# PCB-CMB-5-SHLD.net
KiCad netlist of a schematic drawn in EAGLE
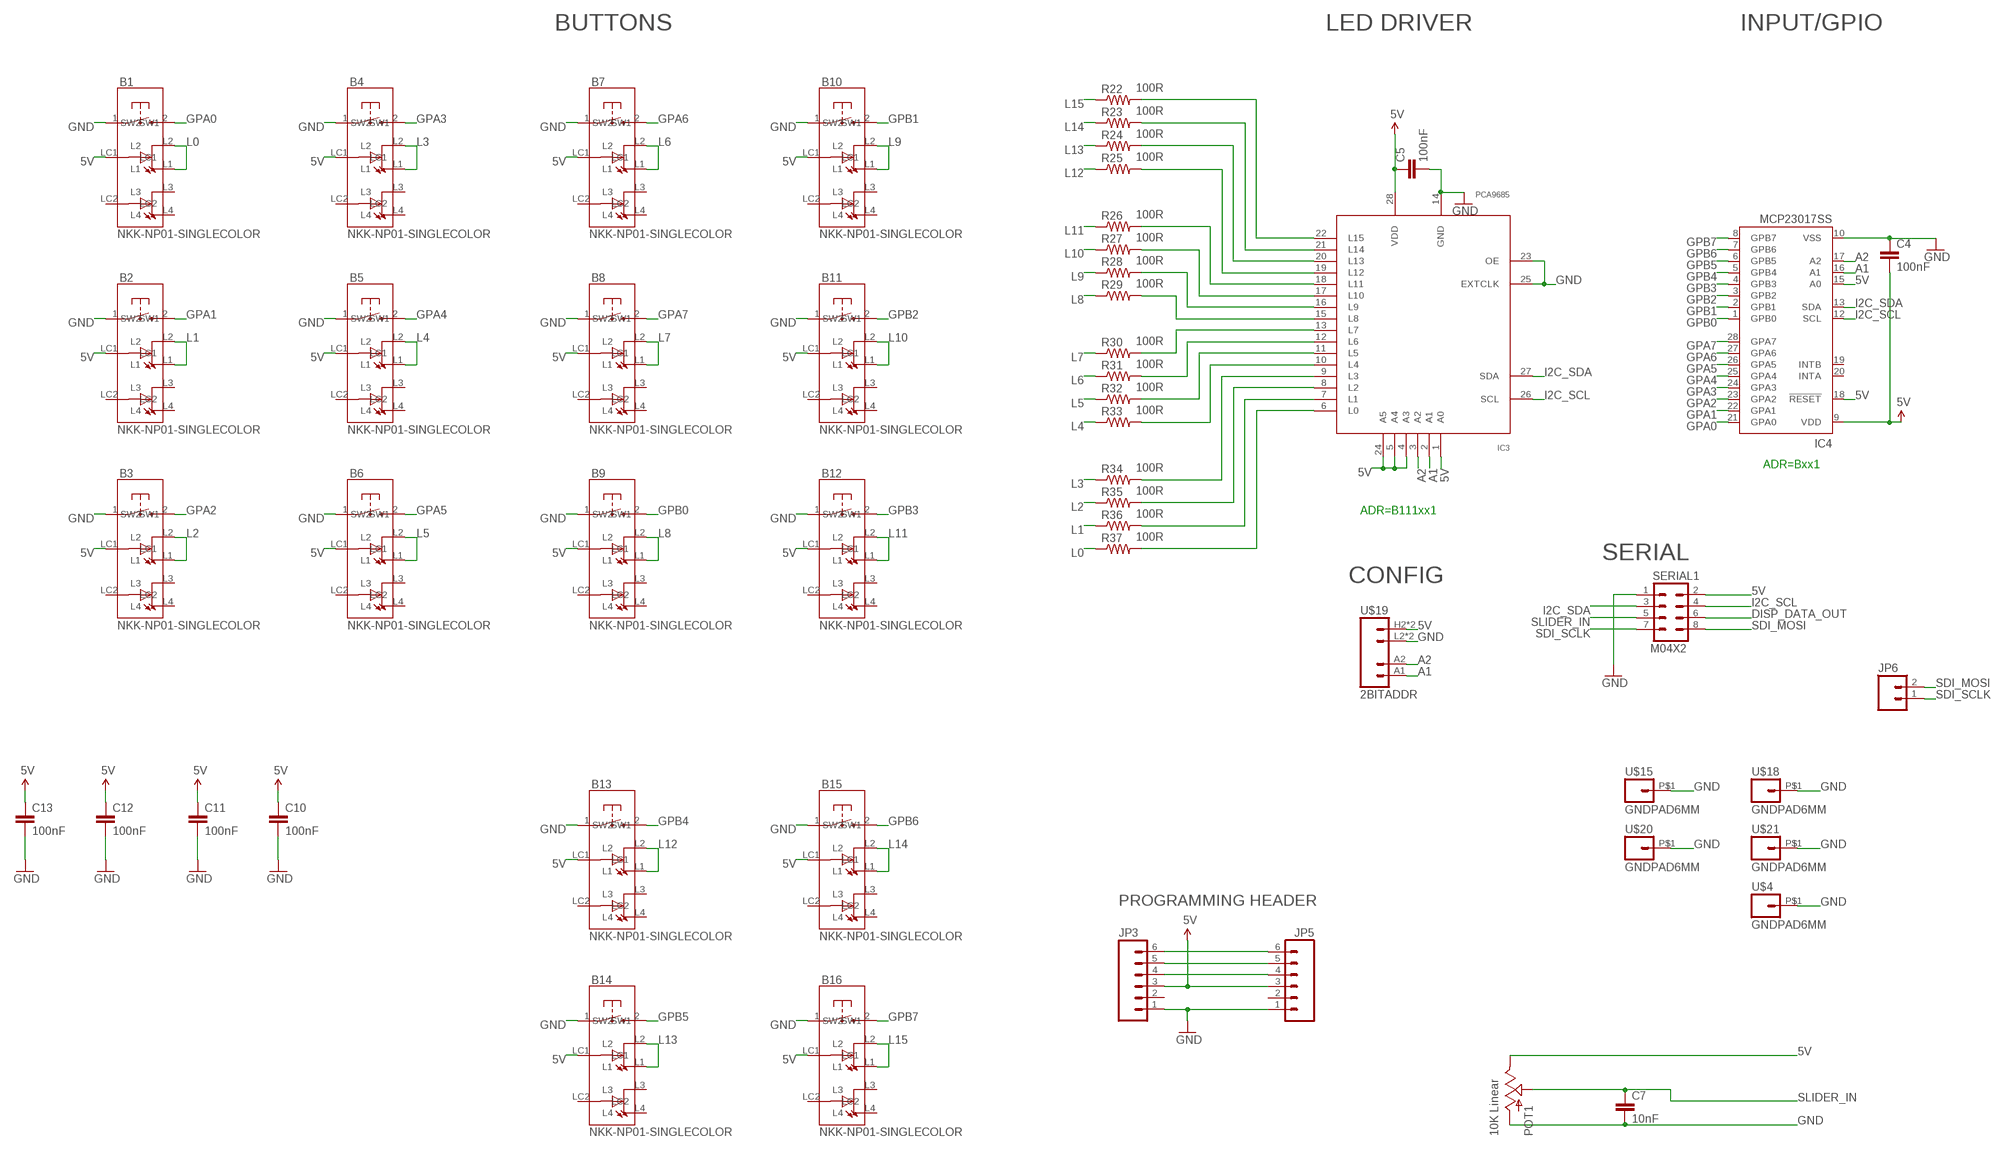
[diagram p0: schematic, sheet 1, part 1 of 3]
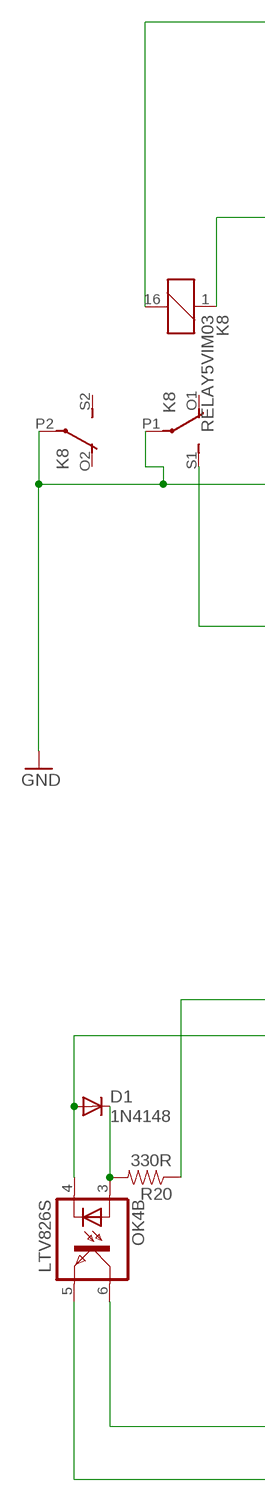
[diagram p1: schematic, sheet 1, part 2 of 3]
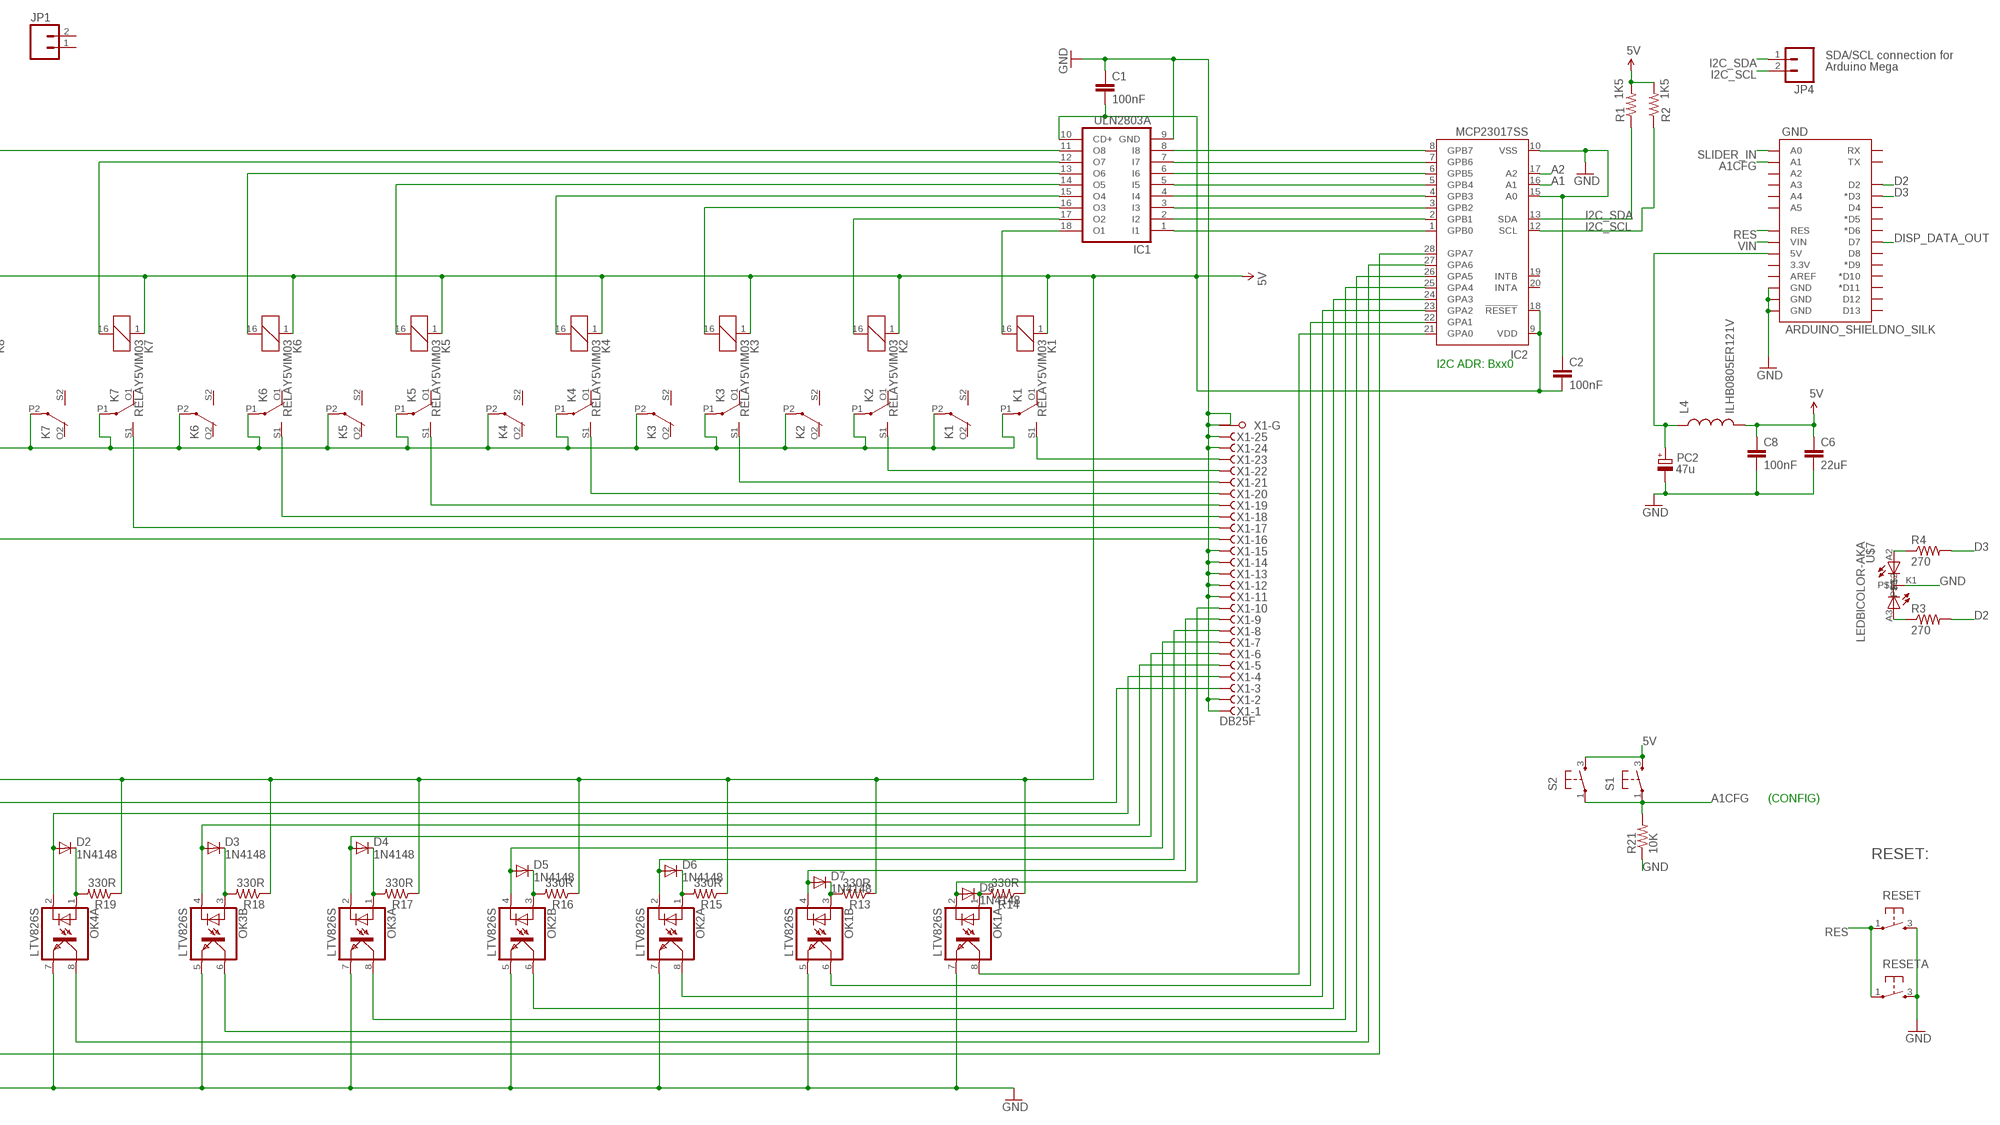
[diagram p2: schematic, sheet 1, part 3 of 3]

(export (version "E")
  (design (tool "Eeschema 10.0.6"))
  (components
    (comp (ref "B1")
      (value "NKK-NP01-SINGLECOLOR")
      (footprint "eagle-import:NKK-NP01")
      (libsource (lib "eagle-import") (part "NKK-NP01-SINGLECOLOR"))
    )
    (comp (ref "B2")
      (value "NKK-NP01-SINGLECOLOR")
      (footprint "eagle-import:NKK-NP01")
      (libsource (lib "eagle-import") (part "NKK-NP01-SINGLECOLOR"))
    )
    (comp (ref "B3")
      (value "NKK-NP01-SINGLECOLOR")
      (footprint "eagle-import:NKK-NP01")
      (libsource (lib "eagle-import") (part "NKK-NP01-SINGLECOLOR"))
    )
    (comp (ref "B4")
      (value "NKK-NP01-SINGLECOLOR")
      (footprint "eagle-import:NKK-NP01")
      (libsource (lib "eagle-import") (part "NKK-NP01-SINGLECOLOR"))
    )
    (comp (ref "B5")
      (value "NKK-NP01-SINGLECOLOR")
      (footprint "eagle-import:NKK-NP01")
      (libsource (lib "eagle-import") (part "NKK-NP01-SINGLECOLOR"))
    )
    (comp (ref "B6")
      (value "NKK-NP01-SINGLECOLOR")
      (footprint "eagle-import:NKK-NP01")
      (libsource (lib "eagle-import") (part "NKK-NP01-SINGLECOLOR"))
    )
    (comp (ref "B7")
      (value "NKK-NP01-SINGLECOLOR")
      (footprint "eagle-import:NKK-NP01")
      (libsource (lib "eagle-import") (part "NKK-NP01-SINGLECOLOR"))
    )
    (comp (ref "B8")
      (value "NKK-NP01-SINGLECOLOR")
      (footprint "eagle-import:NKK-NP01")
      (libsource (lib "eagle-import") (part "NKK-NP01-SINGLECOLOR"))
    )
    (comp (ref "B9")
      (value "NKK-NP01-SINGLECOLOR")
      (footprint "eagle-import:NKK-NP01")
      (libsource (lib "eagle-import") (part "NKK-NP01-SINGLECOLOR"))
    )
    (comp (ref "B10")
      (value "NKK-NP01-SINGLECOLOR")
      (footprint "eagle-import:NKK-NP01")
      (libsource (lib "eagle-import") (part "NKK-NP01-SINGLECOLOR"))
    )
    (comp (ref "B11")
      (value "NKK-NP01-SINGLECOLOR")
      (footprint "eagle-import:NKK-NP01")
      (libsource (lib "eagle-import") (part "NKK-NP01-SINGLECOLOR"))
    )
    (comp (ref "B12")
      (value "NKK-NP01-SINGLECOLOR")
      (footprint "eagle-import:NKK-NP01")
      (libsource (lib "eagle-import") (part "NKK-NP01-SINGLECOLOR"))
    )
    (comp (ref "B13")
      (value "NKK-NP01-SINGLECOLOR")
      (footprint "eagle-import:NKK-NP01")
      (libsource (lib "eagle-import") (part "NKK-NP01-SINGLECOLOR"))
    )
    (comp (ref "B14")
      (value "NKK-NP01-SINGLECOLOR")
      (footprint "eagle-import:NKK-NP01")
      (libsource (lib "eagle-import") (part "NKK-NP01-SINGLECOLOR"))
    )
    (comp (ref "B15")
      (value "NKK-NP01-SINGLECOLOR")
      (footprint "eagle-import:NKK-NP01")
      (libsource (lib "eagle-import") (part "NKK-NP01-SINGLECOLOR"))
    )
    (comp (ref "B16")
      (value "NKK-NP01-SINGLECOLOR")
      (footprint "eagle-import:NKK-NP01")
      (libsource (lib "eagle-import") (part "NKK-NP01-SINGLECOLOR"))
    )
    (comp (ref "C1")
      (value "100nF")
      (footprint "eagle-import:0805")
      (libsource (lib "eagle-import") (part "CAP0805"))
    )
    (comp (ref "C2")
      (value "100nF")
      (footprint "eagle-import:0603-CAP")
      (libsource (lib "eagle-import") (part "CAP0603-CAP"))
    )
    (comp (ref "C4")
      (value "100nF")
      (footprint "eagle-import:0603-CAP")
      (libsource (lib "eagle-import") (part "CAP0603-CAP"))
    )
    (comp (ref "C5")
      (value "100nF")
      (footprint "eagle-import:0603-CAP")
      (libsource (lib "eagle-import") (part "CAP0603-CAP"))
    )
    (comp (ref "C6")
      (value "22uF")
      (footprint "eagle-import:0805")
      (libsource (lib "eagle-import") (part "CAP0805"))
    )
    (comp (ref "C7")
      (value "10nF")
      (footprint "eagle-import:0603-CAP")
      (libsource (lib "eagle-import") (part "CAP0603-CAP"))
    )
    (comp (ref "C8")
      (value "100nF")
      (footprint "eagle-import:0603-CAP")
      (libsource (lib "eagle-import") (part "CAP0603-CAP"))
    )
    (comp (ref "C10")
      (value "100nF")
      (footprint "eagle-import:0603-CAP")
      (libsource (lib "eagle-import") (part "CAP0603-CAP"))
    )
    (comp (ref "C11")
      (value "100nF")
      (footprint "eagle-import:0603-CAP")
      (libsource (lib "eagle-import") (part "CAP0603-CAP"))
    )
    (comp (ref "C12")
      (value "100nF")
      (footprint "eagle-import:0603-CAP")
      (libsource (lib "eagle-import") (part "CAP0603-CAP"))
    )
    (comp (ref "C13")
      (value "100nF")
      (footprint "eagle-import:0603-CAP")
      (libsource (lib "eagle-import") (part "CAP0603-CAP"))
    )
    (comp (ref "D1")
      (value "1N4148")
      (footprint "eagle-import:SOD-323")
      (libsource (lib "eagle-import") (part "DIODESOD"))
    )
    (comp (ref "D2")
      (value "1N4148")
      (footprint "eagle-import:SOD-323")
      (libsource (lib "eagle-import") (part "DIODESOD"))
    )
    (comp (ref "D3")
      (value "1N4148")
      (footprint "eagle-import:SOD-323")
      (libsource (lib "eagle-import") (part "DIODESOD"))
    )
    (comp (ref "D4")
      (value "1N4148")
      (footprint "eagle-import:SOD-323")
      (libsource (lib "eagle-import") (part "DIODESOD"))
    )
    (comp (ref "D5")
      (value "1N4148")
      (footprint "eagle-import:SOD-323")
      (libsource (lib "eagle-import") (part "DIODESOD"))
    )
    (comp (ref "D6")
      (value "1N4148")
      (footprint "eagle-import:SOD-323")
      (libsource (lib "eagle-import") (part "DIODESOD"))
    )
    (comp (ref "D7")
      (value "1N4148")
      (footprint "eagle-import:SOD-323")
      (libsource (lib "eagle-import") (part "DIODESOD"))
    )
    (comp (ref "D8")
      (value "1N4148")
      (footprint "eagle-import:SOD-323")
      (libsource (lib "eagle-import") (part "DIODESOD"))
    )
    (comp (ref "GND")
      (value "ARDUINO_SHIELDNO_SILK")
      (footprint "eagle-import:DUEMILANOVE_VIAS")
      (libsource (lib "eagle-import") (part "ARDUINO_SHIELDNO_SILK"))
    )
    (comp (ref "IC1")
      (value "ULN2803A")
      (footprint "eagle-import:SO18W")
      (libsource (lib "eagle-import") (part "ULN2803ASO18W"))
    )
    (comp (ref "IC2")
      (value "MCP23017SS")
      (footprint "eagle-import:SSOP28")
      (fields (field (name "MF") "MICROCHIP") (field (name "MPN") "MCP23017-E/SS"))
      (libsource (lib "eagle-import") (part "MCP23017SS"))
    )
    (comp (ref "IC3")
      (value "PCA9685")
      (footprint "eagle-import:TSSOP28")
      (libsource (lib "eagle-import") (part "PCA9685"))
    )
    (comp (ref "IC4")
      (value "MCP23017SS")
      (footprint "eagle-import:SSOP28")
      (fields
        (field (name "MF") "MICROCHIP")
        (field (name "MPN") "MCP23017-E/SS")
        (field (name "MPN_1") "MCP23017-E/SS")
        (field (name "OC_FARNELL") "1467674")
        (field (name "OC_NEWARK") "31K2960")
      )
      (libsource (lib "eagle-import") (part "MCP23017SS"))
    )
    (comp (ref "JP1")
      (value "M02PTH")
      (footprint "eagle-import:1X02")
      (libsource (lib "eagle-import") (part "M02PTH"))
    )
    (comp (ref "JP3")
      (value "M06POLAR")
      (footprint "eagle-import:MOLEX-1X6")
      (libsource (lib "eagle-import") (part "M06POLAR"))
    )
    (comp (ref "JP4")
      (value "M02PTH")
      (footprint "eagle-import:1X02")
      (libsource (lib "eagle-import") (part "M02PTH"))
    )
    (comp (ref "JP5")
      (value "M06POLAR")
      (footprint "eagle-import:MOLEX-1X6")
      (libsource (lib "eagle-import") (part "M06POLAR"))
    )
    (comp (ref "JP6")
      (value "M02PTH")
      (footprint "eagle-import:1X02")
      (libsource (lib "eagle-import") (part "M02PTH"))
    )
    (comp (ref "K1")
      (value "RELAY5VIM03")
      (footprint "eagle-import:DS2Y")
      (libsource (lib "eagle-import") (part "RELAY5VIM03"))
    )
    (comp (ref "K2")
      (value "RELAY5VIM03")
      (footprint "eagle-import:DS2Y")
      (libsource (lib "eagle-import") (part "RELAY5VIM03"))
    )
    (comp (ref "K3")
      (value "RELAY5VIM03")
      (footprint "eagle-import:DS2Y")
      (libsource (lib "eagle-import") (part "RELAY5VIM03"))
    )
    (comp (ref "K4")
      (value "RELAY5VIM03")
      (footprint "eagle-import:DS2Y")
      (libsource (lib "eagle-import") (part "RELAY5VIM03"))
    )
    (comp (ref "K5")
      (value "RELAY5VIM03")
      (footprint "eagle-import:DS2Y")
      (libsource (lib "eagle-import") (part "RELAY5VIM03"))
    )
    (comp (ref "K6")
      (value "RELAY5VIM03")
      (footprint "eagle-import:DS2Y")
      (libsource (lib "eagle-import") (part "RELAY5VIM03"))
    )
    (comp (ref "K7")
      (value "RELAY5VIM03")
      (footprint "eagle-import:DS2Y")
      (libsource (lib "eagle-import") (part "RELAY5VIM03"))
    )
    (comp (ref "K8")
      (value "RELAY5VIM03")
      (footprint "eagle-import:DS2Y")
      (libsource (lib "eagle-import") (part "RELAY5VIM03"))
    )
    (comp (ref "L4")
      (value "ILHB0805ER121V")
      (footprint "eagle-import:0805")
      (libsource (lib "eagle-import") (part "INDUCTOR0805"))
    )
    (comp (ref "OK1")
      (value "LTV826S")
      (footprint "eagle-import:DIL8-SMD")
      (libsource (lib "eagle-import") (part "LTV826S"))
    )
    (comp (ref "OK2")
      (value "LTV826S")
      (footprint "eagle-import:DIL8-SMD")
      (libsource (lib "eagle-import") (part "LTV826S"))
    )
    (comp (ref "OK3")
      (value "LTV826S")
      (footprint "eagle-import:DIL8-SMD")
      (libsource (lib "eagle-import") (part "LTV826S"))
    )
    (comp (ref "OK4")
      (value "LTV826S")
      (footprint "eagle-import:DIL8-SMD")
      (libsource (lib "eagle-import") (part "LTV826S"))
    )
    (comp (ref "PC2")
      (value "47u")
      (footprint "eagle-import:PANASONIC_D")
      (libsource (lib "eagle-import") (part "CPOL-EUD"))
    )
    (comp (ref "POT1")
      (value "10K Linear")
      (footprint "eagle-import:SLIDER20")
      (libsource (lib "eagle-import") (part "SLIDER20"))
    )
    (comp (ref "R1")
      (value "1K5")
      (footprint "eagle-import:0603-RES")
      (libsource (lib "eagle-import") (part "RESISTOR0603-RES"))
    )
    (comp (ref "R2")
      (value "1K5")
      (footprint "eagle-import:0603-RES")
      (libsource (lib "eagle-import") (part "RESISTOR0603-RES"))
    )
    (comp (ref "R3")
      (value "270")
      (footprint "eagle-import:0603-RES")
      (libsource (lib "eagle-import") (part "RESISTOR0603-RES"))
    )
    (comp (ref "R4")
      (value "270")
      (footprint "eagle-import:0603-RES")
      (libsource (lib "eagle-import") (part "RESISTOR0603-RES"))
    )
    (comp (ref "R13")
      (value "330R")
      (footprint "eagle-import:0603-RES")
      (libsource (lib "eagle-import") (part "RESISTOR0603-RES"))
    )
    (comp (ref "R14")
      (value "330R")
      (footprint "eagle-import:0603-RES")
      (libsource (lib "eagle-import") (part "RESISTOR0603-RES"))
    )
    (comp (ref "R15")
      (value "330R")
      (footprint "eagle-import:0603-RES")
      (libsource (lib "eagle-import") (part "RESISTOR0603-RES"))
    )
    (comp (ref "R16")
      (value "330R")
      (footprint "eagle-import:0603-RES")
      (libsource (lib "eagle-import") (part "RESISTOR0603-RES"))
    )
    (comp (ref "R17")
      (value "330R")
      (footprint "eagle-import:0603-RES")
      (libsource (lib "eagle-import") (part "RESISTOR0603-RES"))
    )
    (comp (ref "R18")
      (value "330R")
      (footprint "eagle-import:0603-RES")
      (libsource (lib "eagle-import") (part "RESISTOR0603-RES"))
    )
    (comp (ref "R19")
      (value "330R")
      (footprint "eagle-import:0603-RES")
      (libsource (lib "eagle-import") (part "RESISTOR0603-RES"))
    )
    (comp (ref "R20")
      (value "330R")
      (footprint "eagle-import:0603-RES")
      (libsource (lib "eagle-import") (part "RESISTOR0603-RES"))
    )
    (comp (ref "R21")
      (value "10K")
      (footprint "eagle-import:0603-RES")
      (libsource (lib "eagle-import") (part "RESISTOR0603-RES"))
    )
    (comp (ref "R22")
      (value "100R")
      (footprint "eagle-import:0603-RES")
      (libsource (lib "eagle-import") (part "RESISTOR0603-RES"))
    )
    (comp (ref "R23")
      (value "100R")
      (footprint "eagle-import:0603-RES")
      (libsource (lib "eagle-import") (part "RESISTOR0603-RES"))
    )
    (comp (ref "R24")
      (value "100R")
      (footprint "eagle-import:0603-RES")
      (libsource (lib "eagle-import") (part "RESISTOR0603-RES"))
    )
    (comp (ref "R25")
      (value "100R")
      (footprint "eagle-import:0603-RES")
      (libsource (lib "eagle-import") (part "RESISTOR0603-RES"))
    )
    (comp (ref "R26")
      (value "100R")
      (footprint "eagle-import:0603-RES")
      (libsource (lib "eagle-import") (part "RESISTOR0603-RES"))
    )
    (comp (ref "R27")
      (value "100R")
      (footprint "eagle-import:0603-RES")
      (libsource (lib "eagle-import") (part "RESISTOR0603-RES"))
    )
    (comp (ref "R28")
      (value "100R")
      (footprint "eagle-import:0603-RES")
      (libsource (lib "eagle-import") (part "RESISTOR0603-RES"))
    )
    (comp (ref "R29")
      (value "100R")
      (footprint "eagle-import:0603-RES")
      (libsource (lib "eagle-import") (part "RESISTOR0603-RES"))
    )
    (comp (ref "R30")
      (value "100R")
      (footprint "eagle-import:0603-RES")
      (libsource (lib "eagle-import") (part "RESISTOR0603-RES"))
    )
    (comp (ref "R31")
      (value "100R")
      (footprint "eagle-import:0603-RES")
      (libsource (lib "eagle-import") (part "RESISTOR0603-RES"))
    )
    (comp (ref "R32")
      (value "100R")
      (footprint "eagle-import:0603-RES")
      (libsource (lib "eagle-import") (part "RESISTOR0603-RES"))
    )
    (comp (ref "R33")
      (value "100R")
      (footprint "eagle-import:0603-RES")
      (libsource (lib "eagle-import") (part "RESISTOR0603-RES"))
    )
    (comp (ref "R34")
      (value "100R")
      (footprint "eagle-import:0603-RES")
      (libsource (lib "eagle-import") (part "RESISTOR0603-RES"))
    )
    (comp (ref "R35")
      (value "100R")
      (footprint "eagle-import:0603-RES")
      (libsource (lib "eagle-import") (part "RESISTOR0603-RES"))
    )
    (comp (ref "R36")
      (value "100R")
      (footprint "eagle-import:0603-RES")
      (libsource (lib "eagle-import") (part "RESISTOR0603-RES"))
    )
    (comp (ref "R37")
      (value "100R")
      (footprint "eagle-import:0603-RES")
      (libsource (lib "eagle-import") (part "RESISTOR0603-RES"))
    )
    (comp (ref "RESET")
      (value "TAC_SWITCH")
      (footprint "eagle-import:PUSHBUTTON")
      (libsource (lib "eagle-import") (part "TAC_SWITCH"))
    )
    (comp (ref "RESETA")
      (value "TAC_SWITCH")
      (footprint "eagle-import:PUSHBUTTON")
      (libsource (lib "eagle-import") (part "TAC_SWITCH"))
    )
    (comp (ref "S1")
      (value "TAC_SWITCH")
      (footprint "eagle-import:PUSHBUTTON")
      (libsource (lib "eagle-import") (part "TAC_SWITCH"))
    )
    (comp (ref "S2")
      (value "TAC_SWITCH")
      (footprint "eagle-import:PUSHBUTTON")
      (libsource (lib "eagle-import") (part "TAC_SWITCH"))
    )
    (comp (ref "SERIAL1")
      (value "M04X2")
      (footprint "eagle-import:2X4")
      (libsource (lib "eagle-import") (part "M04X2"))
    )
    (comp (ref "U$4")
      (value "GNDPAD6MM")
      (footprint "eagle-import:3.2MMPAD6MM")
      (libsource (lib "eagle-import") (part "GNDPAD6MM"))
    )
    (comp (ref "U$7")
      (value "LEDBICOLOR-AKA")
      (footprint "eagle-import:LED5MM-BICOLOR")
      (libsource (lib "eagle-import") (part "LEDBICOLOR-AKA"))
    )
    (comp (ref "U$15")
      (value "GNDPAD6MM")
      (footprint "eagle-import:3.2MMPAD6MM")
      (libsource (lib "eagle-import") (part "GNDPAD6MM"))
    )
    (comp (ref "U$18")
      (value "GNDPAD6MM")
      (footprint "eagle-import:3.2MMPAD6MM")
      (libsource (lib "eagle-import") (part "GNDPAD6MM"))
    )
    (comp (ref "U$19")
      (value "2BITADDR")
      (footprint "eagle-import:2BITADDR")
      (libsource (lib "eagle-import") (part "2BITADDR"))
    )
    (comp (ref "U$20")
      (value "GNDPAD6MM")
      (footprint "eagle-import:3.2MMPAD6MM")
      (libsource (lib "eagle-import") (part "GNDPAD6MM"))
    )
    (comp (ref "U$21")
      (value "GNDPAD6MM")
      (footprint "eagle-import:3.2MMPAD6MM")
      (libsource (lib "eagle-import") (part "GNDPAD6MM"))
    )
    (comp (ref "X1")
      (value "DB25F")
      (footprint "eagle-import:F25HP")
      (libsource (lib "eagle-import") (part "F25HPS"))
    )
  )
  (nets
    (net (code "1") (name "5V") (class "Default")
      (node (ref "B1") (pin "LC1") (pinfunction "LC1_LC1") (pintype "bidirectional"))
      (node (ref "B10") (pin "LC1") (pinfunction "LC1_LC1") (pintype "bidirectional"))
      (node (ref "B11") (pin "LC1") (pinfunction "LC1_LC1") (pintype "bidirectional"))
      (node (ref "B12") (pin "LC1") (pinfunction "LC1_LC1") (pintype "bidirectional"))
      (node (ref "B13") (pin "LC1") (pinfunction "LC1_LC1") (pintype "bidirectional"))
      (node (ref "B14") (pin "LC1") (pinfunction "LC1_LC1") (pintype "bidirectional"))
      (node (ref "B15") (pin "LC1") (pinfunction "LC1_LC1") (pintype "bidirectional"))
      (node (ref "B16") (pin "LC1") (pinfunction "LC1_LC1") (pintype "bidirectional"))
      (node (ref "B2") (pin "LC1") (pinfunction "LC1_LC1") (pintype "bidirectional"))
      (node (ref "B3") (pin "LC1") (pinfunction "LC1_LC1") (pintype "bidirectional"))
      (node (ref "B4") (pin "LC1") (pinfunction "LC1_LC1") (pintype "bidirectional"))
      (node (ref "B5") (pin "LC1") (pinfunction "LC1_LC1") (pintype "bidirectional"))
      (node (ref "B6") (pin "LC1") (pinfunction "LC1_LC1") (pintype "bidirectional"))
      (node (ref "B7") (pin "LC1") (pinfunction "LC1_LC1") (pintype "bidirectional"))
      (node (ref "B8") (pin "LC1") (pinfunction "LC1_LC1") (pintype "bidirectional"))
      (node (ref "B9") (pin "LC1") (pinfunction "LC1_LC1") (pintype "bidirectional"))
      (node (ref "C1") (pin "2") (pinfunction "2_2") (pintype "passive"))
      (node (ref "C10") (pin "1") (pinfunction "1_1") (pintype "passive"))
      (node (ref "C11") (pin "1") (pinfunction "1_1") (pintype "passive"))
      (node (ref "C12") (pin "1") (pinfunction "1_1") (pintype "passive"))
      (node (ref "C13") (pin "1") (pinfunction "1_1") (pintype "passive"))
      (node (ref "C2") (pin "2") (pinfunction "2_2") (pintype "passive"))
      (node (ref "C4") (pin "2") (pinfunction "2_2") (pintype "passive"))
      (node (ref "C5") (pin "1") (pinfunction "1_1") (pintype "passive"))
      (node (ref "C6") (pin "1") (pinfunction "1_1") (pintype "passive"))
      (node (ref "C8") (pin "1") (pinfunction "1_1") (pintype "passive"))
      (node (ref "IC1") (pin "10") (pinfunction "CD+_10") (pintype "passive"))
      (node (ref "IC2") (pin "18") (pinfunction "~{RESET}_18") (pintype "input"))
      (node (ref "IC2") (pin "9") (pinfunction "VDD_9") (pintype "power_in"))
      (node (ref "IC3") (pin "1") (pinfunction "A0_1") (pintype "input"))
      (node (ref "IC3") (pin "24") (pinfunction "A5_24") (pintype "input"))
      (node (ref "IC3") (pin "28") (pinfunction "VDD_28") (pintype "power_in"))
      (node (ref "IC3") (pin "4") (pinfunction "A3_4") (pintype "input"))
      (node (ref "IC3") (pin "5") (pinfunction "A4_5") (pintype "input"))
      (node (ref "IC4") (pin "15") (pinfunction "A0_15") (pintype "input"))
      (node (ref "IC4") (pin "18") (pinfunction "~{RESET}_18") (pintype "input"))
      (node (ref "IC4") (pin "9") (pinfunction "VDD_9") (pintype "power_in"))
      (node (ref "JP3") (pin "3") (pinfunction "3_3") (pintype "passive"))
      (node (ref "JP5") (pin "3") (pinfunction "3_3") (pintype "passive"))
      (node (ref "K1") (pin "1") (pinfunction "1_1") (pintype "passive"))
      (node (ref "K2") (pin "1") (pinfunction "1_1") (pintype "passive"))
      (node (ref "K3") (pin "1") (pinfunction "1_1") (pintype "passive"))
      (node (ref "K4") (pin "1") (pinfunction "1_1") (pintype "passive"))
      (node (ref "K5") (pin "1") (pinfunction "1_1") (pintype "passive"))
      (node (ref "K6") (pin "1") (pinfunction "1_1") (pintype "passive"))
      (node (ref "K7") (pin "1") (pinfunction "1_1") (pintype "passive"))
      (node (ref "K8") (pin "1") (pinfunction "1_1") (pintype "passive"))
      (node (ref "L4") (pin "2") (pinfunction "2_2") (pintype "passive"))
      (node (ref "POT1") (pin "1") (pinfunction "E_1") (pintype "passive"))
      (node (ref "R1") (pin "2") (pinfunction "2_2") (pintype "passive"))
      (node (ref "R13") (pin "1") (pinfunction "1_1") (pintype "passive"))
      (node (ref "R14") (pin "1") (pinfunction "1_1") (pintype "passive"))
      (node (ref "R15") (pin "1") (pinfunction "1_1") (pintype "passive"))
      (node (ref "R16") (pin "1") (pinfunction "1_1") (pintype "passive"))
      (node (ref "R17") (pin "1") (pinfunction "1_1") (pintype "passive"))
      (node (ref "R18") (pin "1") (pinfunction "1_1") (pintype "passive"))
      (node (ref "R19") (pin "1") (pinfunction "1_1") (pintype "passive"))
      (node (ref "R2") (pin "2") (pinfunction "2_2") (pintype "passive"))
      (node (ref "R20") (pin "1") (pinfunction "1_1") (pintype "passive"))
      (node (ref "S1") (pin "3") (pinfunction "3_3") (pintype "passive"))
      (node (ref "S2") (pin "3") (pinfunction "3_3") (pintype "passive"))
      (node (ref "SERIAL1") (pin "2") (pinfunction "2_2") (pintype "passive"))
      (node (ref "U$19") (pin "H2") (pinfunction "VCC_H2") (pintype "passive"))
      (node (ref "U$19") (pin "H3") (pinfunction "VCC_H3") (pintype "passive"))
    )
    (net (code "2") (name "A1") (class "Default")
      (node (ref "IC2") (pin "16") (pinfunction "A1_16") (pintype "input"))
      (node (ref "IC3") (pin "2") (pinfunction "A1_2") (pintype "input"))
      (node (ref "IC4") (pin "16") (pinfunction "A1_16") (pintype "input"))
      (node (ref "U$19") (pin "A1") (pinfunction "A1_A1") (pintype "passive"))
    )
    (net (code "3") (name "A1CFG") (class "Default")
      (node (ref "GND") (pin "A1") (pinfunction "A1_A1") (pintype "bidirectional"))
      (node (ref "R21") (pin "2") (pinfunction "2_2") (pintype "passive"))
      (node (ref "S1") (pin "1") (pinfunction "1_1") (pintype "passive"))
      (node (ref "S2") (pin "1") (pinfunction "1_1") (pintype "passive"))
    )
    (net (code "4") (name "A2") (class "Default")
      (node (ref "IC2") (pin "17") (pinfunction "A2_17") (pintype "input"))
      (node (ref "IC3") (pin "3") (pinfunction "A2_3") (pintype "input"))
      (node (ref "IC4") (pin "17") (pinfunction "A2_17") (pintype "input"))
      (node (ref "U$19") (pin "A2") (pinfunction "A2_A2") (pintype "passive"))
    )
    (net (code "5") (name "D2") (class "Default")
      (node (ref "GND") (pin "D2") (pinfunction "D2_D2") (pintype "bidirectional"))
      (node (ref "R3") (pin "2") (pinfunction "2_2") (pintype "passive"))
    )
    (net (code "6") (name "D3") (class "Default")
      (node (ref "GND") (pin "D3") (pinfunction "*D3_D3") (pintype "bidirectional"))
      (node (ref "R4") (pin "2") (pinfunction "2_2") (pintype "passive"))
    )
    (net (code "7") (name "DISP_DATA_OUT") (class "Default")
      (node (ref "GND") (pin "D7") (pinfunction "D7_D7") (pintype "bidirectional"))
      (node (ref "SERIAL1") (pin "6") (pinfunction "6_6") (pintype "passive"))
    )
    (net (code "8") (name "GND") (class "Default")
      (node (ref "B1") (pin "1") (pinfunction "SW1_1") (pintype "bidirectional"))
      (node (ref "B10") (pin "1") (pinfunction "SW1_1") (pintype "bidirectional"))
      (node (ref "B11") (pin "1") (pinfunction "SW1_1") (pintype "bidirectional"))
      (node (ref "B12") (pin "1") (pinfunction "SW1_1") (pintype "bidirectional"))
      (node (ref "B13") (pin "1") (pinfunction "SW1_1") (pintype "bidirectional"))
      (node (ref "B14") (pin "1") (pinfunction "SW1_1") (pintype "bidirectional"))
      (node (ref "B15") (pin "1") (pinfunction "SW1_1") (pintype "bidirectional"))
      (node (ref "B16") (pin "1") (pinfunction "SW1_1") (pintype "bidirectional"))
      (node (ref "B2") (pin "1") (pinfunction "SW1_1") (pintype "bidirectional"))
      (node (ref "B3") (pin "1") (pinfunction "SW1_1") (pintype "bidirectional"))
      (node (ref "B4") (pin "1") (pinfunction "SW1_1") (pintype "bidirectional"))
      (node (ref "B5") (pin "1") (pinfunction "SW1_1") (pintype "bidirectional"))
      (node (ref "B6") (pin "1") (pinfunction "SW1_1") (pintype "bidirectional"))
      (node (ref "B7") (pin "1") (pinfunction "SW1_1") (pintype "bidirectional"))
      (node (ref "B8") (pin "1") (pinfunction "SW1_1") (pintype "bidirectional"))
      (node (ref "B9") (pin "1") (pinfunction "SW1_1") (pintype "bidirectional"))
      (node (ref "C1") (pin "1") (pinfunction "1_1") (pintype "passive"))
      (node (ref "C10") (pin "2") (pinfunction "2_2") (pintype "passive"))
      (node (ref "C11") (pin "2") (pinfunction "2_2") (pintype "passive"))
      (node (ref "C12") (pin "2") (pinfunction "2_2") (pintype "passive"))
      (node (ref "C13") (pin "2") (pinfunction "2_2") (pintype "passive"))
      (node (ref "C2") (pin "1") (pinfunction "1_1") (pintype "passive"))
      (node (ref "C4") (pin "1") (pinfunction "1_1") (pintype "passive"))
      (node (ref "C5") (pin "2") (pinfunction "2_2") (pintype "passive"))
      (node (ref "C6") (pin "2") (pinfunction "2_2") (pintype "passive"))
      (node (ref "C7") (pin "2") (pinfunction "2_2") (pintype "passive"))
      (node (ref "C8") (pin "2") (pinfunction "2_2") (pintype "passive"))
      (node (ref "GND") (pin "GND@0") (pinfunction "GND_GND@0") (pintype "bidirectional"))
      (node (ref "GND") (pin "GND@1") (pinfunction "GND_GND@1") (pintype "bidirectional"))
      (node (ref "GND") (pin "GND@2") (pinfunction "GND_GND@2") (pintype "bidirectional"))
      (node (ref "IC1") (pin "9") (pinfunction "GND_9") (pintype "power_in"))
      (node (ref "IC2") (pin "10") (pinfunction "VSS_10") (pintype "power_in"))
      (node (ref "IC2") (pin "15") (pinfunction "A0_15") (pintype "input"))
      (node (ref "IC3") (pin "14") (pinfunction "GND_14") (pintype "power_in"))
      (node (ref "IC3") (pin "23") (pinfunction "OE_23") (pintype "input"))
      (node (ref "IC3") (pin "25") (pinfunction "EXTCLK_25") (pintype "input"))
      (node (ref "IC4") (pin "10") (pinfunction "VSS_10") (pintype "power_in"))
      (node (ref "JP3") (pin "1") (pinfunction "1_1") (pintype "passive"))
      (node (ref "JP5") (pin "1") (pinfunction "1_1") (pintype "passive"))
      (node (ref "K1") (pin "P1") (pinfunction "P_P1") (pintype "passive"))
      (node (ref "K1") (pin "P2") (pinfunction "P_P2") (pintype "passive"))
      (node (ref "K2") (pin "P1") (pinfunction "P_P1") (pintype "passive"))
      (node (ref "K2") (pin "P2") (pinfunction "P_P2") (pintype "passive"))
      (node (ref "K3") (pin "P1") (pinfunction "P_P1") (pintype "passive"))
      (node (ref "K3") (pin "P2") (pinfunction "P_P2") (pintype "passive"))
      (node (ref "K4") (pin "P1") (pinfunction "P_P1") (pintype "passive"))
      (node (ref "K4") (pin "P2") (pinfunction "P_P2") (pintype "passive"))
      (node (ref "K5") (pin "P1") (pinfunction "P_P1") (pintype "passive"))
      (node (ref "K5") (pin "P2") (pinfunction "P_P2") (pintype "passive"))
      (node (ref "K6") (pin "P1") (pinfunction "P_P1") (pintype "passive"))
      (node (ref "K6") (pin "P2") (pinfunction "P_P2") (pintype "passive"))
      (node (ref "K7") (pin "P1") (pinfunction "P_P1") (pintype "passive"))
      (node (ref "K7") (pin "P2") (pinfunction "P_P2") (pintype "passive"))
      (node (ref "K8") (pin "P1") (pinfunction "P_P1") (pintype "passive"))
      (node (ref "K8") (pin "P2") (pinfunction "P_P2") (pintype "passive"))
      (node (ref "OK1") (pin "5") (pinfunction "EMIT_5") (pintype "passive"))
      (node (ref "OK1") (pin "7") (pinfunction "EMIT_7") (pintype "passive"))
      (node (ref "OK2") (pin "5") (pinfunction "EMIT_5") (pintype "passive"))
      (node (ref "OK2") (pin "7") (pinfunction "EMIT_7") (pintype "passive"))
      (node (ref "OK3") (pin "5") (pinfunction "EMIT_5") (pintype "passive"))
      (node (ref "OK3") (pin "7") (pinfunction "EMIT_7") (pintype "passive"))
      (node (ref "OK4") (pin "5") (pinfunction "EMIT_5") (pintype "passive"))
      (node (ref "OK4") (pin "7") (pinfunction "EMIT_7") (pintype "passive"))
      (node (ref "PC2") (pin "-") (pinfunction "-_-") (pintype "passive"))
      (node (ref "POT1") (pin "3") (pinfunction "A_3") (pintype "passive"))
      (node (ref "R21") (pin "1") (pinfunction "1_1") (pintype "passive"))
      (node (ref "RESET") (pin "3") (pinfunction "3_3") (pintype "passive"))
      (node (ref "RESETA") (pin "3") (pinfunction "3_3") (pintype "passive"))
      (node (ref "SERIAL1") (pin "1") (pinfunction "1_1") (pintype "passive"))
      (node (ref "U$15") (pin "P$1") (pinfunction "1_P$1") (pintype "passive"))
      (node (ref "U$18") (pin "P$1") (pinfunction "1_P$1") (pintype "passive"))
      (node (ref "U$19") (pin "L2") (pinfunction "GND_L2") (pintype "passive"))
      (node (ref "U$19") (pin "L3") (pinfunction "GND_L3") (pintype "passive"))
      (node (ref "U$20") (pin "P$1") (pinfunction "1_P$1") (pintype "passive"))
      (node (ref "U$21") (pin "P$1") (pinfunction "1_P$1") (pintype "passive"))
      (node (ref "U$4") (pin "P$1") (pinfunction "1_P$1") (pintype "passive"))
      (node (ref "U$7") (pin "K1") (pinfunction "P$1_K1") (pintype "bidirectional"))
      (node (ref "X1") (pin "1") (pinfunction "F_1") (pintype "passive"))
      (node (ref "X1") (pin "11") (pinfunction "F_11") (pintype "passive"))
      (node (ref "X1") (pin "12") (pinfunction "F_12") (pintype "passive"))
      (node (ref "X1") (pin "13") (pinfunction "F_13") (pintype "passive"))
      (node (ref "X1") (pin "14") (pinfunction "F_14") (pintype "passive"))
      (node (ref "X1") (pin "15") (pinfunction "F_15") (pintype "passive"))
      (node (ref "X1") (pin "2") (pinfunction "F_2") (pintype "passive"))
      (node (ref "X1") (pin "24") (pinfunction "F_24") (pintype "passive"))
      (node (ref "X1") (pin "25") (pinfunction "F_25") (pintype "passive"))
      (node (ref "X1") (pin "G1") (pinfunction "G1_G1") (pintype "passive"))
      (node (ref "X1") (pin "G2") (pinfunction "G2_G2") (pintype "passive"))
    )
    (net (code "9") (name "GPA0") (class "Default")
      (node (ref "B1") (pin "2") (pinfunction "SW2_2") (pintype "bidirectional"))
      (node (ref "IC4") (pin "21") (pinfunction "GPA0_21") (pintype "bidirectional"))
    )
    (net (code "10") (name "GPA1") (class "Default")
      (node (ref "B2") (pin "2") (pinfunction "SW2_2") (pintype "bidirectional"))
      (node (ref "IC4") (pin "22") (pinfunction "GPA1_22") (pintype "bidirectional"))
    )
    (net (code "11") (name "GPA2") (class "Default")
      (node (ref "B3") (pin "2") (pinfunction "SW2_2") (pintype "bidirectional"))
      (node (ref "IC4") (pin "23") (pinfunction "GPA2_23") (pintype "bidirectional"))
    )
    (net (code "12") (name "GPA3") (class "Default")
      (node (ref "B4") (pin "2") (pinfunction "SW2_2") (pintype "bidirectional"))
      (node (ref "IC4") (pin "24") (pinfunction "GPA3_24") (pintype "bidirectional"))
    )
    (net (code "13") (name "GPA4") (class "Default")
      (node (ref "B5") (pin "2") (pinfunction "SW2_2") (pintype "bidirectional"))
      (node (ref "IC4") (pin "25") (pinfunction "GPA4_25") (pintype "bidirectional"))
    )
    (net (code "14") (name "GPA5") (class "Default")
      (node (ref "B6") (pin "2") (pinfunction "SW2_2") (pintype "bidirectional"))
      (node (ref "IC4") (pin "26") (pinfunction "GPA5_26") (pintype "bidirectional"))
    )
    (net (code "15") (name "GPA6") (class "Default")
      (node (ref "B7") (pin "2") (pinfunction "SW2_2") (pintype "bidirectional"))
      (node (ref "IC4") (pin "27") (pinfunction "GPA6_27") (pintype "bidirectional"))
    )
    (net (code "16") (name "GPA7") (class "Default")
      (node (ref "B8") (pin "2") (pinfunction "SW2_2") (pintype "bidirectional"))
      (node (ref "IC4") (pin "28") (pinfunction "GPA7_28") (pintype "bidirectional"))
    )
    (net (code "17") (name "GPB0") (class "Default")
      (node (ref "B9") (pin "2") (pinfunction "SW2_2") (pintype "bidirectional"))
      (node (ref "IC4") (pin "1") (pinfunction "GPB0_1") (pintype "bidirectional"))
    )
    (net (code "18") (name "GPB1") (class "Default")
      (node (ref "B10") (pin "2") (pinfunction "SW2_2") (pintype "bidirectional"))
      (node (ref "IC4") (pin "2") (pinfunction "GPB1_2") (pintype "bidirectional"))
    )
    (net (code "19") (name "GPB2") (class "Default")
      (node (ref "B11") (pin "2") (pinfunction "SW2_2") (pintype "bidirectional"))
      (node (ref "IC4") (pin "3") (pinfunction "GPB2_3") (pintype "bidirectional"))
    )
    (net (code "20") (name "GPB3") (class "Default")
      (node (ref "B12") (pin "2") (pinfunction "SW2_2") (pintype "bidirectional"))
      (node (ref "IC4") (pin "4") (pinfunction "GPB3_4") (pintype "bidirectional"))
    )
    (net (code "21") (name "GPB4") (class "Default")
      (node (ref "B13") (pin "2") (pinfunction "SW2_2") (pintype "bidirectional"))
      (node (ref "IC4") (pin "5") (pinfunction "GPB4_5") (pintype "bidirectional"))
    )
    (net (code "22") (name "GPB5") (class "Default")
      (node (ref "B14") (pin "2") (pinfunction "SW2_2") (pintype "bidirectional"))
      (node (ref "IC4") (pin "6") (pinfunction "GPB5_6") (pintype "bidirectional"))
    )
    (net (code "23") (name "GPB6") (class "Default")
      (node (ref "B15") (pin "2") (pinfunction "SW2_2") (pintype "bidirectional"))
      (node (ref "IC4") (pin "7") (pinfunction "GPB6_7") (pintype "bidirectional"))
    )
    (net (code "24") (name "GPB7") (class "Default")
      (node (ref "B16") (pin "2") (pinfunction "SW2_2") (pintype "bidirectional"))
      (node (ref "IC4") (pin "8") (pinfunction "GPB7_8") (pintype "bidirectional"))
    )
    (net (code "25") (name "I2C_SCL") (class "Default")
      (node (ref "IC2") (pin "12") (pinfunction "SCL_12") (pintype "input"))
      (node (ref "IC3") (pin "26") (pinfunction "SCL_26") (pintype "input"))
      (node (ref "IC4") (pin "12") (pinfunction "SCL_12") (pintype "input"))
      (node (ref "JP4") (pin "2") (pinfunction "2_2") (pintype "passive"))
      (node (ref "R2") (pin "1") (pinfunction "1_1") (pintype "passive"))
      (node (ref "SERIAL1") (pin "4") (pinfunction "4_4") (pintype "passive"))
    )
    (net (code "26") (name "I2C_SDA") (class "Default")
      (node (ref "IC2") (pin "13") (pinfunction "SDA_13") (pintype "bidirectional"))
      (node (ref "IC3") (pin "27") (pinfunction "SDA_27") (pintype "input"))
      (node (ref "IC4") (pin "13") (pinfunction "SDA_13") (pintype "bidirectional"))
      (node (ref "JP4") (pin "1") (pinfunction "1_1") (pintype "passive"))
      (node (ref "R1") (pin "1") (pinfunction "1_1") (pintype "passive"))
      (node (ref "SERIAL1") (pin "3") (pinfunction "3_3") (pintype "passive"))
    )
    (net (code "27") (name "L0") (class "Default")
      (node (ref "B1") (pin "L1") (pinfunction "L1_L1") (pintype "bidirectional"))
      (node (ref "B1") (pin "L2") (pinfunction "L2_L2") (pintype "bidirectional"))
      (node (ref "R37") (pin "1") (pinfunction "1_1") (pintype "passive"))
    )
    (net (code "28") (name "L1") (class "Default")
      (node (ref "B2") (pin "L1") (pinfunction "L1_L1") (pintype "bidirectional"))
      (node (ref "B2") (pin "L2") (pinfunction "L2_L2") (pintype "bidirectional"))
      (node (ref "R36") (pin "1") (pinfunction "1_1") (pintype "passive"))
    )
    (net (code "29") (name "L2") (class "Default")
      (node (ref "B3") (pin "L1") (pinfunction "L1_L1") (pintype "bidirectional"))
      (node (ref "B3") (pin "L2") (pinfunction "L2_L2") (pintype "bidirectional"))
      (node (ref "R35") (pin "1") (pinfunction "1_1") (pintype "passive"))
    )
    (net (code "30") (name "L3") (class "Default")
      (node (ref "B4") (pin "L1") (pinfunction "L1_L1") (pintype "bidirectional"))
      (node (ref "B4") (pin "L2") (pinfunction "L2_L2") (pintype "bidirectional"))
      (node (ref "R34") (pin "1") (pinfunction "1_1") (pintype "passive"))
    )
    (net (code "31") (name "L4") (class "Default")
      (node (ref "B5") (pin "L1") (pinfunction "L1_L1") (pintype "bidirectional"))
      (node (ref "B5") (pin "L2") (pinfunction "L2_L2") (pintype "bidirectional"))
      (node (ref "R33") (pin "1") (pinfunction "1_1") (pintype "passive"))
    )
    (net (code "32") (name "L5") (class "Default")
      (node (ref "B6") (pin "L1") (pinfunction "L1_L1") (pintype "bidirectional"))
      (node (ref "B6") (pin "L2") (pinfunction "L2_L2") (pintype "bidirectional"))
      (node (ref "R32") (pin "1") (pinfunction "1_1") (pintype "passive"))
    )
    (net (code "33") (name "L6") (class "Default")
      (node (ref "B7") (pin "L1") (pinfunction "L1_L1") (pintype "bidirectional"))
      (node (ref "B7") (pin "L2") (pinfunction "L2_L2") (pintype "bidirectional"))
      (node (ref "R31") (pin "1") (pinfunction "1_1") (pintype "passive"))
    )
    (net (code "34") (name "L7") (class "Default")
      (node (ref "B8") (pin "L1") (pinfunction "L1_L1") (pintype "bidirectional"))
      (node (ref "B8") (pin "L2") (pinfunction "L2_L2") (pintype "bidirectional"))
      (node (ref "R30") (pin "1") (pinfunction "1_1") (pintype "passive"))
    )
    (net (code "35") (name "L8") (class "Default")
      (node (ref "B9") (pin "L1") (pinfunction "L1_L1") (pintype "bidirectional"))
      (node (ref "B9") (pin "L2") (pinfunction "L2_L2") (pintype "bidirectional"))
      (node (ref "R29") (pin "1") (pinfunction "1_1") (pintype "passive"))
    )
    (net (code "36") (name "L9") (class "Default")
      (node (ref "B10") (pin "L1") (pinfunction "L1_L1") (pintype "bidirectional"))
      (node (ref "B10") (pin "L2") (pinfunction "L2_L2") (pintype "bidirectional"))
      (node (ref "R28") (pin "1") (pinfunction "1_1") (pintype "passive"))
    )
    (net (code "37") (name "L10") (class "Default")
      (node (ref "B11") (pin "L1") (pinfunction "L1_L1") (pintype "bidirectional"))
      (node (ref "B11") (pin "L2") (pinfunction "L2_L2") (pintype "bidirectional"))
      (node (ref "R27") (pin "1") (pinfunction "1_1") (pintype "passive"))
    )
    (net (code "38") (name "L11") (class "Default")
      (node (ref "B12") (pin "L1") (pinfunction "L1_L1") (pintype "bidirectional"))
      (node (ref "B12") (pin "L2") (pinfunction "L2_L2") (pintype "bidirectional"))
      (node (ref "R26") (pin "1") (pinfunction "1_1") (pintype "passive"))
    )
    (net (code "39") (name "L12") (class "Default")
      (node (ref "B13") (pin "L1") (pinfunction "L1_L1") (pintype "bidirectional"))
      (node (ref "B13") (pin "L2") (pinfunction "L2_L2") (pintype "bidirectional"))
      (node (ref "R25") (pin "1") (pinfunction "1_1") (pintype "passive"))
    )
    (net (code "40") (name "L13") (class "Default")
      (node (ref "B14") (pin "L1") (pinfunction "L1_L1") (pintype "bidirectional"))
      (node (ref "B14") (pin "L2") (pinfunction "L2_L2") (pintype "bidirectional"))
      (node (ref "R24") (pin "1") (pinfunction "1_1") (pintype "passive"))
    )
    (net (code "41") (name "L14") (class "Default")
      (node (ref "B15") (pin "L1") (pinfunction "L1_L1") (pintype "bidirectional"))
      (node (ref "B15") (pin "L2") (pinfunction "L2_L2") (pintype "bidirectional"))
      (node (ref "R23") (pin "1") (pinfunction "1_1") (pintype "passive"))
    )
    (net (code "42") (name "L15") (class "Default")
      (node (ref "B16") (pin "L1") (pinfunction "L1_L1") (pintype "bidirectional"))
      (node (ref "B16") (pin "L2") (pinfunction "L2_L2") (pintype "bidirectional"))
      (node (ref "R22") (pin "1") (pinfunction "1_1") (pintype "passive"))
    )
    (net (code "43") (name "Net-(D1-A)") (class "Default")
      (node (ref "D1") (pin "2") (pinfunction "A_2") (pintype "passive"))
      (node (ref "OK4") (pin "4") (pinfunction "C_4") (pintype "passive"))
      (node (ref "X1") (pin "3") (pinfunction "F_3") (pintype "passive"))
    )
    (net (code "44") (name "Net-(D1-C)") (class "Default")
      (node (ref "D1") (pin "1") (pinfunction "C_1") (pintype "passive"))
      (node (ref "OK4") (pin "3") (pinfunction "A_3") (pintype "passive"))
      (node (ref "R20") (pin "2") (pinfunction "2_2") (pintype "passive"))
    )
    (net (code "45") (name "Net-(D2-A)") (class "Default")
      (node (ref "D2") (pin "2") (pinfunction "A_2") (pintype "passive"))
      (node (ref "OK4") (pin "2") (pinfunction "C_2") (pintype "passive"))
      (node (ref "X1") (pin "4") (pinfunction "F_4") (pintype "passive"))
    )
    (net (code "46") (name "Net-(D2-C)") (class "Default")
      (node (ref "D2") (pin "1") (pinfunction "C_1") (pintype "passive"))
      (node (ref "OK4") (pin "1") (pinfunction "A_1") (pintype "passive"))
      (node (ref "R19") (pin "2") (pinfunction "2_2") (pintype "passive"))
    )
    (net (code "47") (name "Net-(D3-A)") (class "Default")
      (node (ref "D3") (pin "2") (pinfunction "A_2") (pintype "passive"))
      (node (ref "OK3") (pin "4") (pinfunction "C_4") (pintype "passive"))
      (node (ref "X1") (pin "5") (pinfunction "F_5") (pintype "passive"))
    )
    (net (code "48") (name "Net-(D3-C)") (class "Default")
      (node (ref "D3") (pin "1") (pinfunction "C_1") (pintype "passive"))
      (node (ref "OK3") (pin "3") (pinfunction "A_3") (pintype "passive"))
      (node (ref "R18") (pin "2") (pinfunction "2_2") (pintype "passive"))
    )
    (net (code "49") (name "Net-(D4-A)") (class "Default")
      (node (ref "D4") (pin "2") (pinfunction "A_2") (pintype "passive"))
      (node (ref "OK3") (pin "2") (pinfunction "C_2") (pintype "passive"))
      (node (ref "X1") (pin "6") (pinfunction "F_6") (pintype "passive"))
    )
    (net (code "50") (name "Net-(D4-C)") (class "Default")
      (node (ref "D4") (pin "1") (pinfunction "C_1") (pintype "passive"))
      (node (ref "OK3") (pin "1") (pinfunction "A_1") (pintype "passive"))
      (node (ref "R17") (pin "2") (pinfunction "2_2") (pintype "passive"))
    )
    (net (code "51") (name "Net-(D5-A)") (class "Default")
      (node (ref "D5") (pin "2") (pinfunction "A_2") (pintype "passive"))
      (node (ref "OK2") (pin "4") (pinfunction "C_4") (pintype "passive"))
      (node (ref "X1") (pin "7") (pinfunction "F_7") (pintype "passive"))
    )
    (net (code "52") (name "Net-(D5-C)") (class "Default")
      (node (ref "D5") (pin "1") (pinfunction "C_1") (pintype "passive"))
      (node (ref "OK2") (pin "3") (pinfunction "A_3") (pintype "passive"))
      (node (ref "R16") (pin "2") (pinfunction "2_2") (pintype "passive"))
    )
    (net (code "53") (name "Net-(D6-A)") (class "Default")
      (node (ref "D6") (pin "2") (pinfunction "A_2") (pintype "passive"))
      (node (ref "OK2") (pin "2") (pinfunction "C_2") (pintype "passive"))
      (node (ref "X1") (pin "8") (pinfunction "F_8") (pintype "passive"))
    )
    (net (code "54") (name "Net-(D6-C)") (class "Default")
      (node (ref "D6") (pin "1") (pinfunction "C_1") (pintype "passive"))
      (node (ref "OK2") (pin "1") (pinfunction "A_1") (pintype "passive"))
      (node (ref "R15") (pin "2") (pinfunction "2_2") (pintype "passive"))
    )
    (net (code "55") (name "Net-(D7-A)") (class "Default")
      (node (ref "D7") (pin "2") (pinfunction "A_2") (pintype "passive"))
      (node (ref "OK1") (pin "4") (pinfunction "C_4") (pintype "passive"))
      (node (ref "X1") (pin "9") (pinfunction "F_9") (pintype "passive"))
    )
    (net (code "56") (name "Net-(D7-C)") (class "Default")
      (node (ref "D7") (pin "1") (pinfunction "C_1") (pintype "passive"))
      (node (ref "OK1") (pin "3") (pinfunction "A_3") (pintype "passive"))
      (node (ref "R13") (pin "2") (pinfunction "2_2") (pintype "passive"))
    )
    (net (code "57") (name "Net-(D8-A)") (class "Default")
      (node (ref "D8") (pin "2") (pinfunction "A_2") (pintype "passive"))
      (node (ref "OK1") (pin "2") (pinfunction "C_2") (pintype "passive"))
      (node (ref "X1") (pin "10") (pinfunction "F_10") (pintype "passive"))
    )
    (net (code "58") (name "Net-(D8-C)") (class "Default")
      (node (ref "D8") (pin "1") (pinfunction "C_1") (pintype "passive"))
      (node (ref "OK1") (pin "1") (pinfunction "A_1") (pintype "passive"))
      (node (ref "R14") (pin "2") (pinfunction "2_2") (pintype "passive"))
    )
    (net (code "59") (name "Net-(GND-Pad5V)") (class "Default")
      (node (ref "GND") (pin "5V") (pinfunction "5V_5V") (pintype "bidirectional"))
      (node (ref "L4") (pin "1") (pinfunction "1_1") (pintype "passive"))
      (node (ref "PC2") (pin "+") (pinfunction "+_+") (pintype "passive"))
    )
    (net (code "60") (name "Net-(IC1-I1)") (class "Default")
      (node (ref "IC1") (pin "1") (pinfunction "I1_1") (pintype "input"))
      (node (ref "IC2") (pin "1") (pinfunction "GPB0_1") (pintype "bidirectional"))
    )
    (net (code "61") (name "Net-(IC1-I2)") (class "Default")
      (node (ref "IC1") (pin "2") (pinfunction "I2_2") (pintype "input"))
      (node (ref "IC2") (pin "2") (pinfunction "GPB1_2") (pintype "bidirectional"))
    )
    (net (code "62") (name "Net-(IC1-I3)") (class "Default")
      (node (ref "IC1") (pin "3") (pinfunction "I3_3") (pintype "input"))
      (node (ref "IC2") (pin "3") (pinfunction "GPB2_3") (pintype "bidirectional"))
    )
    (net (code "63") (name "Net-(IC1-I4)") (class "Default")
      (node (ref "IC1") (pin "4") (pinfunction "I4_4") (pintype "input"))
      (node (ref "IC2") (pin "4") (pinfunction "GPB3_4") (pintype "bidirectional"))
    )
    (net (code "64") (name "Net-(IC1-I5)") (class "Default")
      (node (ref "IC1") (pin "5") (pinfunction "I5_5") (pintype "input"))
      (node (ref "IC2") (pin "5") (pinfunction "GPB4_5") (pintype "bidirectional"))
    )
    (net (code "65") (name "Net-(IC1-I6)") (class "Default")
      (node (ref "IC1") (pin "6") (pinfunction "I6_6") (pintype "input"))
      (node (ref "IC2") (pin "6") (pinfunction "GPB5_6") (pintype "bidirectional"))
    )
    (net (code "66") (name "Net-(IC1-I7)") (class "Default")
      (node (ref "IC1") (pin "7") (pinfunction "I7_7") (pintype "input"))
      (node (ref "IC2") (pin "7") (pinfunction "GPB6_7") (pintype "bidirectional"))
    )
    (net (code "67") (name "Net-(IC1-I8)") (class "Default")
      (node (ref "IC1") (pin "8") (pinfunction "I8_8") (pintype "input"))
      (node (ref "IC2") (pin "8") (pinfunction "GPB7_8") (pintype "bidirectional"))
    )
    (net (code "68") (name "Net-(IC1-O1)") (class "Default")
      (node (ref "IC1") (pin "18") (pinfunction "O1_18") (pintype "open_collector"))
      (node (ref "K1") (pin "16") (pinfunction "2_16") (pintype "passive"))
    )
    (net (code "69") (name "Net-(IC1-O2)") (class "Default")
      (node (ref "IC1") (pin "17") (pinfunction "O2_17") (pintype "open_collector"))
      (node (ref "K2") (pin "16") (pinfunction "2_16") (pintype "passive"))
    )
    (net (code "70") (name "Net-(IC1-O3)") (class "Default")
      (node (ref "IC1") (pin "16") (pinfunction "O3_16") (pintype "open_collector"))
      (node (ref "K3") (pin "16") (pinfunction "2_16") (pintype "passive"))
    )
    (net (code "71") (name "Net-(IC1-O4)") (class "Default")
      (node (ref "IC1") (pin "15") (pinfunction "O4_15") (pintype "open_collector"))
      (node (ref "K4") (pin "16") (pinfunction "2_16") (pintype "passive"))
    )
    (net (code "72") (name "Net-(IC1-O5)") (class "Default")
      (node (ref "IC1") (pin "14") (pinfunction "O5_14") (pintype "open_collector"))
      (node (ref "K5") (pin "16") (pinfunction "2_16") (pintype "passive"))
    )
    (net (code "73") (name "Net-(IC1-O6)") (class "Default")
      (node (ref "IC1") (pin "13") (pinfunction "O6_13") (pintype "open_collector"))
      (node (ref "K6") (pin "16") (pinfunction "2_16") (pintype "passive"))
    )
    (net (code "74") (name "Net-(IC1-O7)") (class "Default")
      (node (ref "IC1") (pin "12") (pinfunction "O7_12") (pintype "open_collector"))
      (node (ref "K7") (pin "16") (pinfunction "2_16") (pintype "passive"))
    )
    (net (code "75") (name "Net-(IC1-O8)") (class "Default")
      (node (ref "IC1") (pin "11") (pinfunction "O8_11") (pintype "open_collector"))
      (node (ref "K8") (pin "16") (pinfunction "2_16") (pintype "passive"))
    )
    (net (code "76") (name "Net-(IC2-GPA0)") (class "Default")
      (node (ref "IC2") (pin "21") (pinfunction "GPA0_21") (pintype "bidirectional"))
      (node (ref "OK1") (pin "8") (pinfunction "COL_8") (pintype "passive"))
    )
    (net (code "77") (name "Net-(IC2-GPA1)") (class "Default")
      (node (ref "IC2") (pin "22") (pinfunction "GPA1_22") (pintype "bidirectional"))
      (node (ref "OK1") (pin "6") (pinfunction "COL_6") (pintype "passive"))
    )
    (net (code "78") (name "Net-(IC2-GPA2)") (class "Default")
      (node (ref "IC2") (pin "23") (pinfunction "GPA2_23") (pintype "bidirectional"))
      (node (ref "OK2") (pin "8") (pinfunction "COL_8") (pintype "passive"))
    )
    (net (code "79") (name "Net-(IC2-GPA3)") (class "Default")
      (node (ref "IC2") (pin "24") (pinfunction "GPA3_24") (pintype "bidirectional"))
      (node (ref "OK2") (pin "6") (pinfunction "COL_6") (pintype "passive"))
    )
    (net (code "80") (name "Net-(IC2-GPA4)") (class "Default")
      (node (ref "IC2") (pin "25") (pinfunction "GPA4_25") (pintype "bidirectional"))
      (node (ref "OK3") (pin "8") (pinfunction "COL_8") (pintype "passive"))
    )
    (net (code "81") (name "Net-(IC2-GPA5)") (class "Default")
      (node (ref "IC2") (pin "26") (pinfunction "GPA5_26") (pintype "bidirectional"))
      (node (ref "OK3") (pin "6") (pinfunction "COL_6") (pintype "passive"))
    )
    (net (code "82") (name "Net-(IC2-GPA6)") (class "Default")
      (node (ref "IC2") (pin "27") (pinfunction "GPA6_27") (pintype "bidirectional"))
      (node (ref "OK4") (pin "8") (pinfunction "COL_8") (pintype "passive"))
    )
    (net (code "83") (name "Net-(IC2-GPA7)") (class "Default")
      (node (ref "IC2") (pin "28") (pinfunction "GPA7_28") (pintype "bidirectional"))
      (node (ref "OK4") (pin "6") (pinfunction "COL_6") (pintype "passive"))
    )
    (net (code "84") (name "Net-(IC3-L0)") (class "Default")
      (node (ref "IC3") (pin "6") (pinfunction "L0_6") (pintype "output"))
      (node (ref "R37") (pin "2") (pinfunction "2_2") (pintype "passive"))
    )
    (net (code "85") (name "Net-(IC3-L1)") (class "Default")
      (node (ref "IC3") (pin "7") (pinfunction "L1_7") (pintype "output"))
      (node (ref "R36") (pin "2") (pinfunction "2_2") (pintype "passive"))
    )
    (net (code "86") (name "Net-(IC3-L2)") (class "Default")
      (node (ref "IC3") (pin "8") (pinfunction "L2_8") (pintype "output"))
      (node (ref "R35") (pin "2") (pinfunction "2_2") (pintype "passive"))
    )
    (net (code "87") (name "Net-(IC3-L3)") (class "Default")
      (node (ref "IC3") (pin "9") (pinfunction "L3_9") (pintype "output"))
      (node (ref "R34") (pin "2") (pinfunction "2_2") (pintype "passive"))
    )
    (net (code "88") (name "Net-(IC3-L4)") (class "Default")
      (node (ref "IC3") (pin "10") (pinfunction "L4_10") (pintype "output"))
      (node (ref "R33") (pin "2") (pinfunction "2_2") (pintype "passive"))
    )
    (net (code "89") (name "Net-(IC3-L5)") (class "Default")
      (node (ref "IC3") (pin "11") (pinfunction "L5_11") (pintype "output"))
      (node (ref "R32") (pin "2") (pinfunction "2_2") (pintype "passive"))
    )
    (net (code "90") (name "Net-(IC3-L6)") (class "Default")
      (node (ref "IC3") (pin "12") (pinfunction "L6_12") (pintype "output"))
      (node (ref "R31") (pin "2") (pinfunction "2_2") (pintype "passive"))
    )
    (net (code "91") (name "Net-(IC3-L7)") (class "Default")
      (node (ref "IC3") (pin "13") (pinfunction "L7_13") (pintype "output"))
      (node (ref "R30") (pin "2") (pinfunction "2_2") (pintype "passive"))
    )
    (net (code "92") (name "Net-(IC3-L8)") (class "Default")
      (node (ref "IC3") (pin "15") (pinfunction "L8_15") (pintype "output"))
      (node (ref "R29") (pin "2") (pinfunction "2_2") (pintype "passive"))
    )
    (net (code "93") (name "Net-(IC3-L9)") (class "Default")
      (node (ref "IC3") (pin "16") (pinfunction "L9_16") (pintype "output"))
      (node (ref "R28") (pin "2") (pinfunction "2_2") (pintype "passive"))
    )
    (net (code "94") (name "Net-(IC3-L10)") (class "Default")
      (node (ref "IC3") (pin "17") (pinfunction "L10_17") (pintype "output"))
      (node (ref "R27") (pin "2") (pinfunction "2_2") (pintype "passive"))
    )
    (net (code "95") (name "Net-(IC3-L11)") (class "Default")
      (node (ref "IC3") (pin "18") (pinfunction "L11_18") (pintype "output"))
      (node (ref "R26") (pin "2") (pinfunction "2_2") (pintype "passive"))
    )
    (net (code "96") (name "Net-(IC3-L12)") (class "Default")
      (node (ref "IC3") (pin "19") (pinfunction "L12_19") (pintype "output"))
      (node (ref "R25") (pin "2") (pinfunction "2_2") (pintype "passive"))
    )
    (net (code "97") (name "Net-(IC3-L13)") (class "Default")
      (node (ref "IC3") (pin "20") (pinfunction "L13_20") (pintype "output"))
      (node (ref "R24") (pin "2") (pinfunction "2_2") (pintype "passive"))
    )
    (net (code "98") (name "Net-(IC3-L14)") (class "Default")
      (node (ref "IC3") (pin "21") (pinfunction "L14_21") (pintype "output"))
      (node (ref "R23") (pin "2") (pinfunction "2_2") (pintype "passive"))
    )
    (net (code "99") (name "Net-(IC3-L15)") (class "Default")
      (node (ref "IC3") (pin "22") (pinfunction "L15_22") (pintype "output"))
      (node (ref "R22") (pin "2") (pinfunction "2_2") (pintype "passive"))
    )
    (net (code "100") (name "Net-(JP3-Pad4)") (class "Default")
      (node (ref "JP3") (pin "4") (pinfunction "4_4") (pintype "passive"))
      (node (ref "JP5") (pin "4") (pinfunction "4_4") (pintype "passive"))
    )
    (net (code "101") (name "Net-(JP3-Pad5)") (class "Default")
      (node (ref "JP3") (pin "5") (pinfunction "5_5") (pintype "passive"))
      (node (ref "JP5") (pin "5") (pinfunction "5_5") (pintype "passive"))
    )
    (net (code "102") (name "Net-(JP3-Pad6)") (class "Default")
      (node (ref "JP3") (pin "6") (pinfunction "6_6") (pintype "passive"))
      (node (ref "JP5") (pin "6") (pinfunction "6_6") (pintype "passive"))
    )
    (net (code "103") (name "Net-(K1B-S)") (class "Default")
      (node (ref "K1") (pin "S1") (pinfunction "S_S1") (pintype "passive"))
      (node (ref "X1") (pin "23") (pinfunction "F_23") (pintype "passive"))
    )
    (net (code "104") (name "Net-(K2B-S)") (class "Default")
      (node (ref "K2") (pin "S1") (pinfunction "S_S1") (pintype "passive"))
      (node (ref "X1") (pin "22") (pinfunction "F_22") (pintype "passive"))
    )
    (net (code "105") (name "Net-(K3B-S)") (class "Default")
      (node (ref "K3") (pin "S1") (pinfunction "S_S1") (pintype "passive"))
      (node (ref "X1") (pin "21") (pinfunction "F_21") (pintype "passive"))
    )
    (net (code "106") (name "Net-(K4B-S)") (class "Default")
      (node (ref "K4") (pin "S1") (pinfunction "S_S1") (pintype "passive"))
      (node (ref "X1") (pin "20") (pinfunction "F_20") (pintype "passive"))
    )
    (net (code "107") (name "Net-(K5B-S)") (class "Default")
      (node (ref "K5") (pin "S1") (pinfunction "S_S1") (pintype "passive"))
      (node (ref "X1") (pin "19") (pinfunction "F_19") (pintype "passive"))
    )
    (net (code "108") (name "Net-(K6B-S)") (class "Default")
      (node (ref "K6") (pin "S1") (pinfunction "S_S1") (pintype "passive"))
      (node (ref "X1") (pin "18") (pinfunction "F_18") (pintype "passive"))
    )
    (net (code "109") (name "Net-(K7B-S)") (class "Default")
      (node (ref "K7") (pin "S1") (pinfunction "S_S1") (pintype "passive"))
      (node (ref "X1") (pin "17") (pinfunction "F_17") (pintype "passive"))
    )
    (net (code "110") (name "Net-(K8B-S)") (class "Default")
      (node (ref "K8") (pin "S1") (pinfunction "S_S1") (pintype "passive"))
      (node (ref "X1") (pin "16") (pinfunction "F_16") (pintype "passive"))
    )
    (net (code "111") (name "Net-(U$7-P$2)") (class "Default")
      (node (ref "R4") (pin "1") (pinfunction "1_1") (pintype "passive"))
      (node (ref "U$7") (pin "A2") (pinfunction "P$2_A2") (pintype "bidirectional"))
    )
    (net (code "112") (name "Net-(U$7-P$3)") (class "Default")
      (node (ref "R3") (pin "1") (pinfunction "1_1") (pintype "passive"))
      (node (ref "U$7") (pin "A3") (pinfunction "P$3_A3") (pintype "bidirectional"))
    )
    (net (code "113") (name "RES") (class "Default")
      (node (ref "GND") (pin "RES") (pinfunction "RES_RES") (pintype "bidirectional"))
      (node (ref "RESET") (pin "1") (pinfunction "1_1") (pintype "passive"))
      (node (ref "RESETA") (pin "1") (pinfunction "1_1") (pintype "passive"))
    )
    (net (code "114") (name "SDI_MOSI") (class "Default")
      (node (ref "JP6") (pin "2") (pinfunction "2_2") (pintype "passive"))
      (node (ref "SERIAL1") (pin "8") (pinfunction "8_8") (pintype "passive"))
    )
    (net (code "115") (name "SDI_SCLK") (class "Default")
      (node (ref "JP6") (pin "1") (pinfunction "1_1") (pintype "passive"))
      (node (ref "SERIAL1") (pin "7") (pinfunction "7_7") (pintype "passive"))
    )
    (net (code "116") (name "SLIDER_IN") (class "Default")
      (node (ref "C7") (pin "1") (pinfunction "1_1") (pintype "passive"))
      (node (ref "GND") (pin "A0") (pinfunction "A0_A0") (pintype "bidirectional"))
      (node (ref "POT1") (pin "2A") (pinfunction "S_2A") (pintype "passive"))
      (node (ref "SERIAL1") (pin "5") (pinfunction "5_5") (pintype "passive"))
    )
    (net (code "117") (name "VIN") (class "Default")
      (node (ref "GND") (pin "VIN") (pinfunction "VIN_VIN") (pintype "bidirectional"))
    )
    (net (code "118") (name "unconnected-(B1-PadL3)") (class "Default")
      (node (ref "B1") (pin "L3") (pinfunction "L3_L3") (pintype "bidirectional"))
    )
    (net (code "119") (name "unconnected-(B1-PadL4)") (class "Default")
      (node (ref "B1") (pin "L4") (pinfunction "L4_L4") (pintype "bidirectional"))
    )
    (net (code "120") (name "unconnected-(B1-PadLC2)") (class "Default")
      (node (ref "B1") (pin "LC2") (pinfunction "LC2_LC2") (pintype "bidirectional"))
    )
    (net (code "121") (name "unconnected-(B2-PadL3)") (class "Default")
      (node (ref "B2") (pin "L3") (pinfunction "L3_L3") (pintype "bidirectional"))
    )
    (net (code "122") (name "unconnected-(B2-PadL4)") (class "Default")
      (node (ref "B2") (pin "L4") (pinfunction "L4_L4") (pintype "bidirectional"))
    )
    (net (code "123") (name "unconnected-(B2-PadLC2)") (class "Default")
      (node (ref "B2") (pin "LC2") (pinfunction "LC2_LC2") (pintype "bidirectional"))
    )
    (net (code "124") (name "unconnected-(B3-PadL3)") (class "Default")
      (node (ref "B3") (pin "L3") (pinfunction "L3_L3") (pintype "bidirectional"))
    )
    (net (code "125") (name "unconnected-(B3-PadL4)") (class "Default")
      (node (ref "B3") (pin "L4") (pinfunction "L4_L4") (pintype "bidirectional"))
    )
    (net (code "126") (name "unconnected-(B3-PadLC2)") (class "Default")
      (node (ref "B3") (pin "LC2") (pinfunction "LC2_LC2") (pintype "bidirectional"))
    )
    (net (code "127") (name "unconnected-(B4-PadL3)") (class "Default")
      (node (ref "B4") (pin "L3") (pinfunction "L3_L3") (pintype "bidirectional"))
    )
    (net (code "128") (name "unconnected-(B4-PadL4)") (class "Default")
      (node (ref "B4") (pin "L4") (pinfunction "L4_L4") (pintype "bidirectional"))
    )
    (net (code "129") (name "unconnected-(B4-PadLC2)") (class "Default")
      (node (ref "B4") (pin "LC2") (pinfunction "LC2_LC2") (pintype "bidirectional"))
    )
    (net (code "130") (name "unconnected-(B5-PadL3)") (class "Default")
      (node (ref "B5") (pin "L3") (pinfunction "L3_L3") (pintype "bidirectional"))
    )
    (net (code "131") (name "unconnected-(B5-PadL4)") (class "Default")
      (node (ref "B5") (pin "L4") (pinfunction "L4_L4") (pintype "bidirectional"))
    )
    (net (code "132") (name "unconnected-(B5-PadLC2)") (class "Default")
      (node (ref "B5") (pin "LC2") (pinfunction "LC2_LC2") (pintype "bidirectional"))
    )
    (net (code "133") (name "unconnected-(B6-PadL3)") (class "Default")
      (node (ref "B6") (pin "L3") (pinfunction "L3_L3") (pintype "bidirectional"))
    )
    (net (code "134") (name "unconnected-(B6-PadL4)") (class "Default")
      (node (ref "B6") (pin "L4") (pinfunction "L4_L4") (pintype "bidirectional"))
    )
    (net (code "135") (name "unconnected-(B6-PadLC2)") (class "Default")
      (node (ref "B6") (pin "LC2") (pinfunction "LC2_LC2") (pintype "bidirectional"))
    )
    (net (code "136") (name "unconnected-(B7-PadL3)") (class "Default")
      (node (ref "B7") (pin "L3") (pinfunction "L3_L3") (pintype "bidirectional"))
    )
    (net (code "137") (name "unconnected-(B7-PadL4)") (class "Default")
      (node (ref "B7") (pin "L4") (pinfunction "L4_L4") (pintype "bidirectional"))
    )
    (net (code "138") (name "unconnected-(B7-PadLC2)") (class "Default")
      (node (ref "B7") (pin "LC2") (pinfunction "LC2_LC2") (pintype "bidirectional"))
    )
    (net (code "139") (name "unconnected-(B8-PadL3)") (class "Default")
      (node (ref "B8") (pin "L3") (pinfunction "L3_L3") (pintype "bidirectional"))
    )
    (net (code "140") (name "unconnected-(B8-PadL4)") (class "Default")
      (node (ref "B8") (pin "L4") (pinfunction "L4_L4") (pintype "bidirectional"))
    )
    (net (code "141") (name "unconnected-(B8-PadLC2)") (class "Default")
      (node (ref "B8") (pin "LC2") (pinfunction "LC2_LC2") (pintype "bidirectional"))
    )
    (net (code "142") (name "unconnected-(B9-PadL3)") (class "Default")
      (node (ref "B9") (pin "L3") (pinfunction "L3_L3") (pintype "bidirectional"))
    )
    (net (code "143") (name "unconnected-(B9-PadL4)") (class "Default")
      (node (ref "B9") (pin "L4") (pinfunction "L4_L4") (pintype "bidirectional"))
    )
    (net (code "144") (name "unconnected-(B9-PadLC2)") (class "Default")
      (node (ref "B9") (pin "LC2") (pinfunction "LC2_LC2") (pintype "bidirectional"))
    )
    (net (code "145") (name "unconnected-(B10-PadL3)") (class "Default")
      (node (ref "B10") (pin "L3") (pinfunction "L3_L3") (pintype "bidirectional"))
    )
    (net (code "146") (name "unconnected-(B10-PadL4)") (class "Default")
      (node (ref "B10") (pin "L4") (pinfunction "L4_L4") (pintype "bidirectional"))
    )
    (net (code "147") (name "unconnected-(B10-PadLC2)") (class "Default")
      (node (ref "B10") (pin "LC2") (pinfunction "LC2_LC2") (pintype "bidirectional"))
    )
    (net (code "148") (name "unconnected-(B11-PadL3)") (class "Default")
      (node (ref "B11") (pin "L3") (pinfunction "L3_L3") (pintype "bidirectional"))
    )
    (net (code "149") (name "unconnected-(B11-PadL4)") (class "Default")
      (node (ref "B11") (pin "L4") (pinfunction "L4_L4") (pintype "bidirectional"))
    )
    (net (code "150") (name "unconnected-(B11-PadLC2)") (class "Default")
      (node (ref "B11") (pin "LC2") (pinfunction "LC2_LC2") (pintype "bidirectional"))
    )
    (net (code "151") (name "unconnected-(B12-PadL3)") (class "Default")
      (node (ref "B12") (pin "L3") (pinfunction "L3_L3") (pintype "bidirectional"))
    )
    (net (code "152") (name "unconnected-(B12-PadL4)") (class "Default")
      (node (ref "B12") (pin "L4") (pinfunction "L4_L4") (pintype "bidirectional"))
    )
    (net (code "153") (name "unconnected-(B12-PadLC2)") (class "Default")
      (node (ref "B12") (pin "LC2") (pinfunction "LC2_LC2") (pintype "bidirectional"))
    )
    (net (code "154") (name "unconnected-(B13-PadL3)") (class "Default")
      (node (ref "B13") (pin "L3") (pinfunction "L3_L3") (pintype "bidirectional"))
    )
    (net (code "155") (name "unconnected-(B13-PadL4)") (class "Default")
      (node (ref "B13") (pin "L4") (pinfunction "L4_L4") (pintype "bidirectional"))
    )
    (net (code "156") (name "unconnected-(B13-PadLC2)") (class "Default")
      (node (ref "B13") (pin "LC2") (pinfunction "LC2_LC2") (pintype "bidirectional"))
    )
    (net (code "157") (name "unconnected-(B14-PadL3)") (class "Default")
      (node (ref "B14") (pin "L3") (pinfunction "L3_L3") (pintype "bidirectional"))
    )
    (net (code "158") (name "unconnected-(B14-PadL4)") (class "Default")
      (node (ref "B14") (pin "L4") (pinfunction "L4_L4") (pintype "bidirectional"))
    )
    (net (code "159") (name "unconnected-(B14-PadLC2)") (class "Default")
      (node (ref "B14") (pin "LC2") (pinfunction "LC2_LC2") (pintype "bidirectional"))
    )
    (net (code "160") (name "unconnected-(B15-PadL3)") (class "Default")
      (node (ref "B15") (pin "L3") (pinfunction "L3_L3") (pintype "bidirectional"))
    )
    (net (code "161") (name "unconnected-(B15-PadL4)") (class "Default")
      (node (ref "B15") (pin "L4") (pinfunction "L4_L4") (pintype "bidirectional"))
    )
    (net (code "162") (name "unconnected-(B15-PadLC2)") (class "Default")
      (node (ref "B15") (pin "LC2") (pinfunction "LC2_LC2") (pintype "bidirectional"))
    )
    (net (code "163") (name "unconnected-(B16-PadL3)") (class "Default")
      (node (ref "B16") (pin "L3") (pinfunction "L3_L3") (pintype "bidirectional"))
    )
    (net (code "164") (name "unconnected-(B16-PadL4)") (class "Default")
      (node (ref "B16") (pin "L4") (pinfunction "L4_L4") (pintype "bidirectional"))
    )
    (net (code "165") (name "unconnected-(B16-PadLC2)") (class "Default")
      (node (ref "B16") (pin "LC2") (pinfunction "LC2_LC2") (pintype "bidirectional"))
    )
    (net (code "166") (name "unconnected-(GND-*D5-PadD5)") (class "Default")
      (node (ref "GND") (pin "D5") (pinfunction "*D5_D5") (pintype "bidirectional"))
    )
    (net (code "167") (name "unconnected-(GND-*D6-PadD6)") (class "Default")
      (node (ref "GND") (pin "D6") (pinfunction "*D6_D6") (pintype "bidirectional"))
    )
    (net (code "168") (name "unconnected-(GND-*D9-PadD9)") (class "Default")
      (node (ref "GND") (pin "D9") (pinfunction "*D9_D9") (pintype "bidirectional"))
    )
    (net (code "169") (name "unconnected-(GND-*D10-PadD10)") (class "Default")
      (node (ref "GND") (pin "D10") (pinfunction "*D10_D10") (pintype "bidirectional"))
    )
    (net (code "170") (name "unconnected-(GND-*D11-PadD11)") (class "Default")
      (node (ref "GND") (pin "D11") (pinfunction "*D11_D11") (pintype "bidirectional"))
    )
    (net (code "171") (name "unconnected-(GND-Pad3.3V)") (class "Default")
      (node (ref "GND") (pin "3.3V") (pinfunction "3.3V_3.3V") (pintype "bidirectional"))
    )
    (net (code "172") (name "unconnected-(GND-PadA2)") (class "Default")
      (node (ref "GND") (pin "A2") (pinfunction "A2_A2") (pintype "bidirectional"))
    )
    (net (code "173") (name "unconnected-(GND-PadA3)") (class "Default")
      (node (ref "GND") (pin "A3") (pinfunction "A3_A3") (pintype "bidirectional"))
    )
    (net (code "174") (name "unconnected-(GND-PadA4)") (class "Default")
      (node (ref "GND") (pin "A4") (pinfunction "A4_A4") (pintype "bidirectional"))
    )
    (net (code "175") (name "unconnected-(GND-PadA5)") (class "Default")
      (node (ref "GND") (pin "A5") (pinfunction "A5_A5") (pintype "bidirectional"))
    )
    (net (code "176") (name "unconnected-(GND-PadAREF)") (class "Default")
      (node (ref "GND") (pin "AREF") (pinfunction "AREF_AREF") (pintype "bidirectional"))
    )
    (net (code "177") (name "unconnected-(GND-PadD4)") (class "Default")
      (node (ref "GND") (pin "D4") (pinfunction "D4_D4") (pintype "bidirectional"))
    )
    (net (code "178") (name "unconnected-(GND-PadD8)") (class "Default")
      (node (ref "GND") (pin "D8") (pinfunction "D8_D8") (pintype "bidirectional"))
    )
    (net (code "179") (name "unconnected-(GND-PadD12)") (class "Default")
      (node (ref "GND") (pin "D12") (pinfunction "D12_D12") (pintype "bidirectional"))
    )
    (net (code "180") (name "unconnected-(GND-PadD13)") (class "Default")
      (node (ref "GND") (pin "D13") (pinfunction "D13_D13") (pintype "bidirectional"))
    )
    (net (code "181") (name "unconnected-(GND-PadRX)") (class "Default")
      (node (ref "GND") (pin "RX") (pinfunction "RX_RX") (pintype "bidirectional"))
    )
    (net (code "182") (name "unconnected-(GND-PadTX)") (class "Default")
      (node (ref "GND") (pin "TX") (pinfunction "TX_TX") (pintype "bidirectional"))
    )
    (net (code "183") (name "unconnected-(IC2-INTA-Pad20)") (class "Default")
      (node (ref "IC2") (pin "20") (pinfunction "INTA_20") (pintype "output"))
    )
    (net (code "184") (name "unconnected-(IC2-INTB-Pad19)") (class "Default")
      (node (ref "IC2") (pin "19") (pinfunction "INTB_19") (pintype "output"))
    )
    (net (code "185") (name "unconnected-(IC4-INTA-Pad20)") (class "Default")
      (node (ref "IC4") (pin "20") (pinfunction "INTA_20") (pintype "output"))
    )
    (net (code "186") (name "unconnected-(IC4-INTB-Pad19)") (class "Default")
      (node (ref "IC4") (pin "19") (pinfunction "INTB_19") (pintype "output"))
    )
    (net (code "187") (name "unconnected-(JP1-Pad1)") (class "Default")
      (node (ref "JP1") (pin "1") (pinfunction "1_1") (pintype "passive"))
    )
    (net (code "188") (name "unconnected-(JP1-Pad2)") (class "Default")
      (node (ref "JP1") (pin "2") (pinfunction "2_2") (pintype "passive"))
    )
    (net (code "189") (name "unconnected-(JP3-Pad2)") (class "Default")
      (node (ref "JP3") (pin "2") (pinfunction "2_2") (pintype "passive"))
    )
    (net (code "190") (name "unconnected-(JP5-Pad2)") (class "Default")
      (node (ref "JP5") (pin "2") (pinfunction "2_2") (pintype "passive"))
    )
    (net (code "191") (name "unconnected-(K1B-O-PadO1)") (class "Default")
      (node (ref "K1") (pin "O1") (pinfunction "O_O1") (pintype "passive"))
    )
    (net (code "192") (name "unconnected-(K1C-O-PadO2)") (class "Default")
      (node (ref "K1") (pin "O2") (pinfunction "O_O2") (pintype "passive"))
    )
    (net (code "193") (name "unconnected-(K1C-S-PadS2)") (class "Default")
      (node (ref "K1") (pin "S2") (pinfunction "S_S2") (pintype "passive"))
    )
    (net (code "194") (name "unconnected-(K2B-O-PadO1)") (class "Default")
      (node (ref "K2") (pin "O1") (pinfunction "O_O1") (pintype "passive"))
    )
    (net (code "195") (name "unconnected-(K2C-O-PadO2)") (class "Default")
      (node (ref "K2") (pin "O2") (pinfunction "O_O2") (pintype "passive"))
    )
    (net (code "196") (name "unconnected-(K2C-S-PadS2)") (class "Default")
      (node (ref "K2") (pin "S2") (pinfunction "S_S2") (pintype "passive"))
    )
    (net (code "197") (name "unconnected-(K3B-O-PadO1)") (class "Default")
      (node (ref "K3") (pin "O1") (pinfunction "O_O1") (pintype "passive"))
    )
    (net (code "198") (name "unconnected-(K3C-O-PadO2)") (class "Default")
      (node (ref "K3") (pin "O2") (pinfunction "O_O2") (pintype "passive"))
    )
    (net (code "199") (name "unconnected-(K3C-S-PadS2)") (class "Default")
      (node (ref "K3") (pin "S2") (pinfunction "S_S2") (pintype "passive"))
    )
    (net (code "200") (name "unconnected-(K4B-O-PadO1)") (class "Default")
      (node (ref "K4") (pin "O1") (pinfunction "O_O1") (pintype "passive"))
    )
    (net (code "201") (name "unconnected-(K4C-O-PadO2)") (class "Default")
      (node (ref "K4") (pin "O2") (pinfunction "O_O2") (pintype "passive"))
    )
    (net (code "202") (name "unconnected-(K4C-S-PadS2)") (class "Default")
      (node (ref "K4") (pin "S2") (pinfunction "S_S2") (pintype "passive"))
    )
    (net (code "203") (name "unconnected-(K5B-O-PadO1)") (class "Default")
      (node (ref "K5") (pin "O1") (pinfunction "O_O1") (pintype "passive"))
    )
    (net (code "204") (name "unconnected-(K5C-O-PadO2)") (class "Default")
      (node (ref "K5") (pin "O2") (pinfunction "O_O2") (pintype "passive"))
    )
    (net (code "205") (name "unconnected-(K5C-S-PadS2)") (class "Default")
      (node (ref "K5") (pin "S2") (pinfunction "S_S2") (pintype "passive"))
    )
    (net (code "206") (name "unconnected-(K6B-O-PadO1)") (class "Default")
      (node (ref "K6") (pin "O1") (pinfunction "O_O1") (pintype "passive"))
    )
    (net (code "207") (name "unconnected-(K6C-O-PadO2)") (class "Default")
      (node (ref "K6") (pin "O2") (pinfunction "O_O2") (pintype "passive"))
    )
    (net (code "208") (name "unconnected-(K6C-S-PadS2)") (class "Default")
      (node (ref "K6") (pin "S2") (pinfunction "S_S2") (pintype "passive"))
    )
    (net (code "209") (name "unconnected-(K7B-O-PadO1)") (class "Default")
      (node (ref "K7") (pin "O1") (pinfunction "O_O1") (pintype "passive"))
    )
    (net (code "210") (name "unconnected-(K7C-O-PadO2)") (class "Default")
      (node (ref "K7") (pin "O2") (pinfunction "O_O2") (pintype "passive"))
    )
    (net (code "211") (name "unconnected-(K7C-S-PadS2)") (class "Default")
      (node (ref "K7") (pin "S2") (pinfunction "S_S2") (pintype "passive"))
    )
    (net (code "212") (name "unconnected-(K8B-O-PadO1)") (class "Default")
      (node (ref "K8") (pin "O1") (pinfunction "O_O1") (pintype "passive"))
    )
    (net (code "213") (name "unconnected-(K8C-O-PadO2)") (class "Default")
      (node (ref "K8") (pin "O2") (pinfunction "O_O2") (pintype "passive"))
    )
    (net (code "214") (name "unconnected-(K8C-S-PadS2)") (class "Default")
      (node (ref "K8") (pin "S2") (pinfunction "S_S2") (pintype "passive"))
    )
  )
)
